# logic.net
KiCad netlist of a schematic drawn in EAGLE
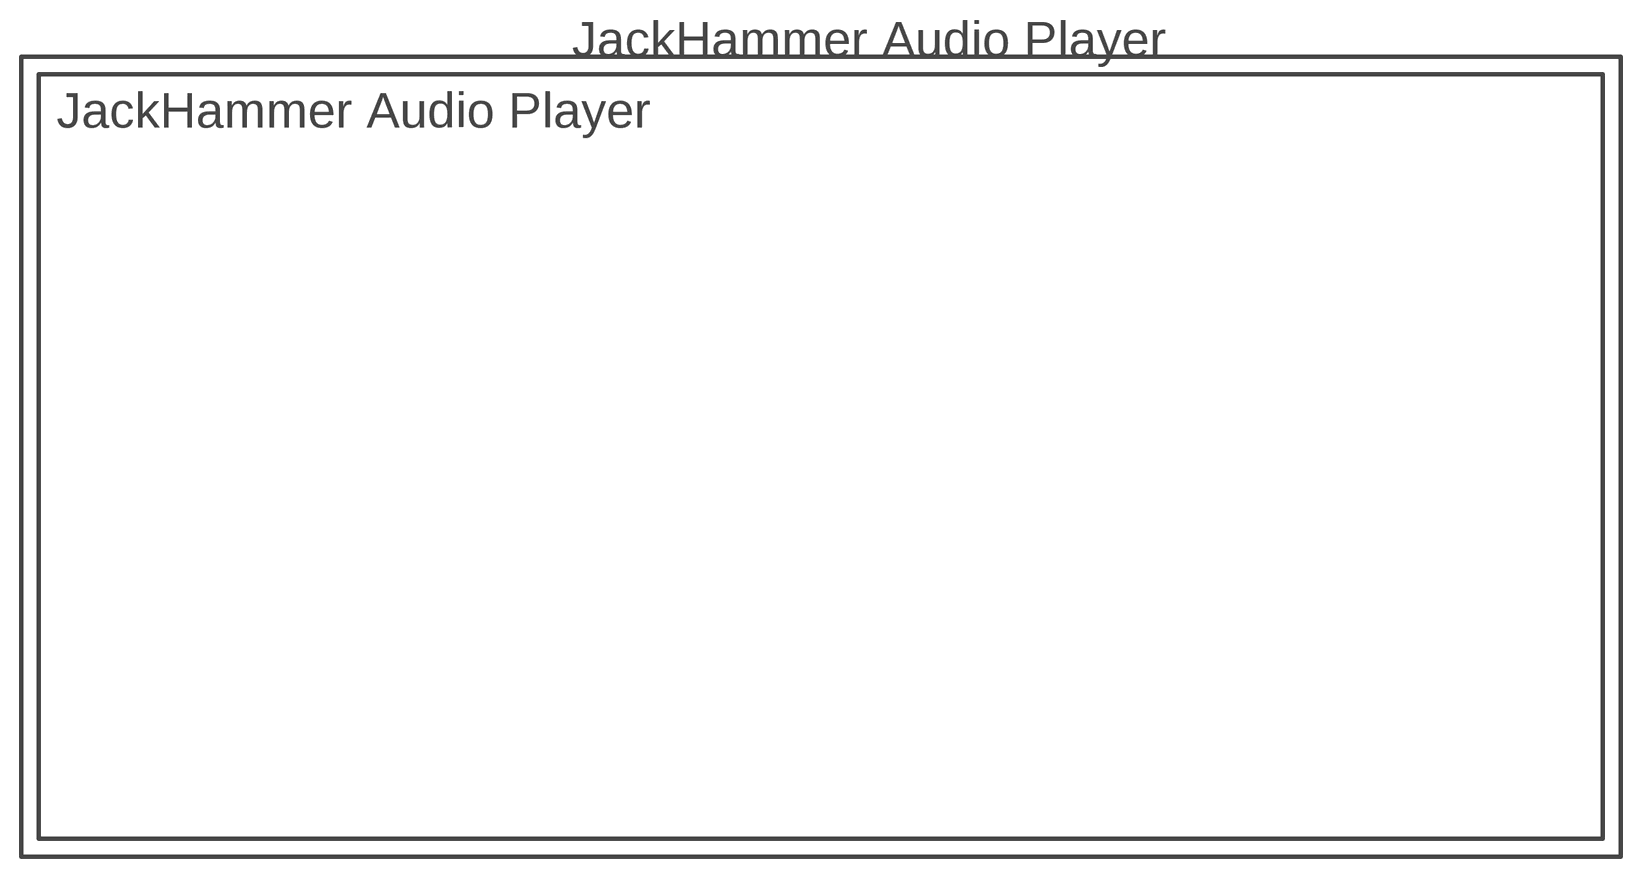
[diagram p0: schematic, sheet 1]
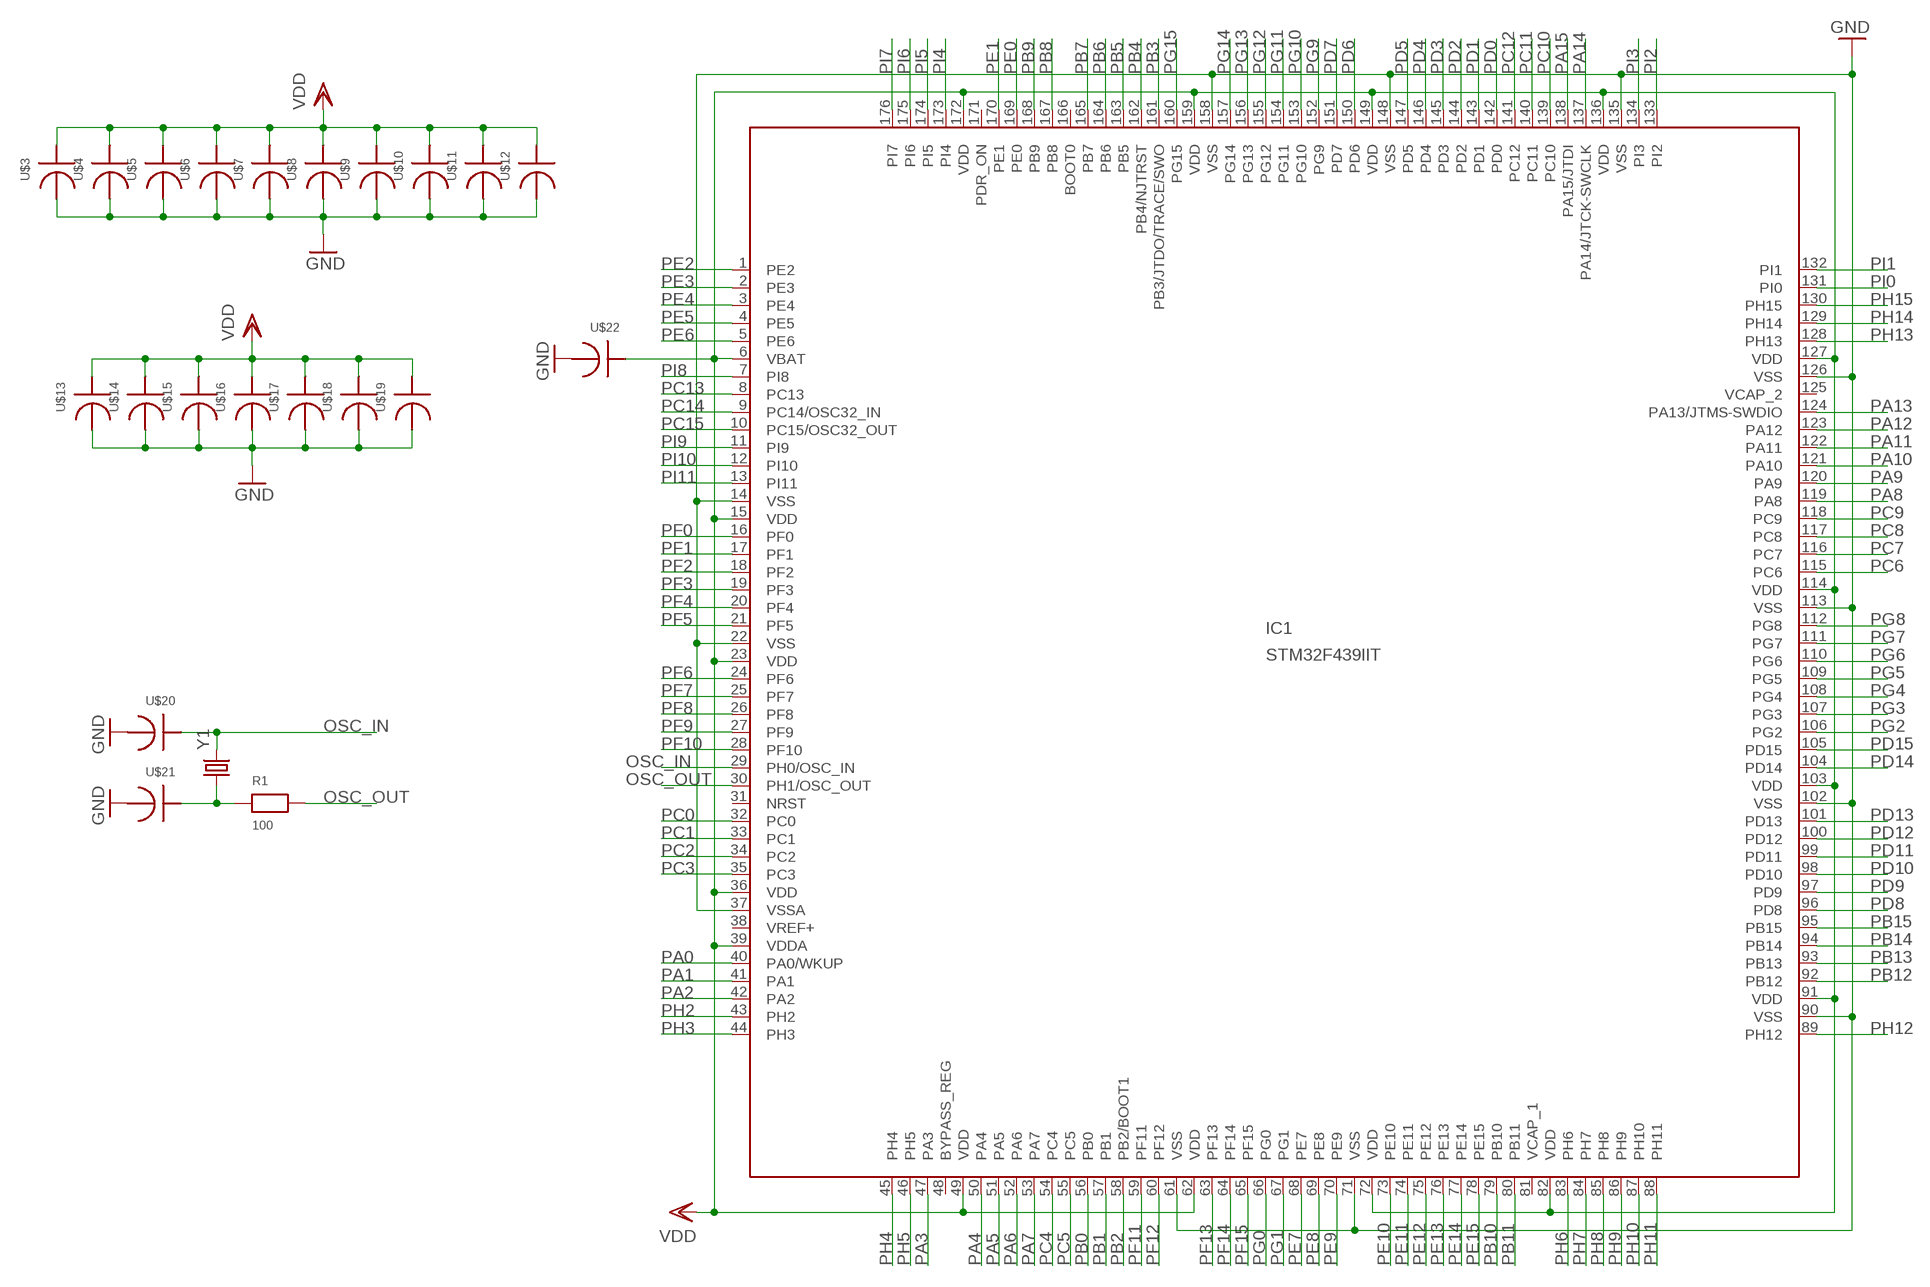
[diagram p1: schematic, sheet 2]
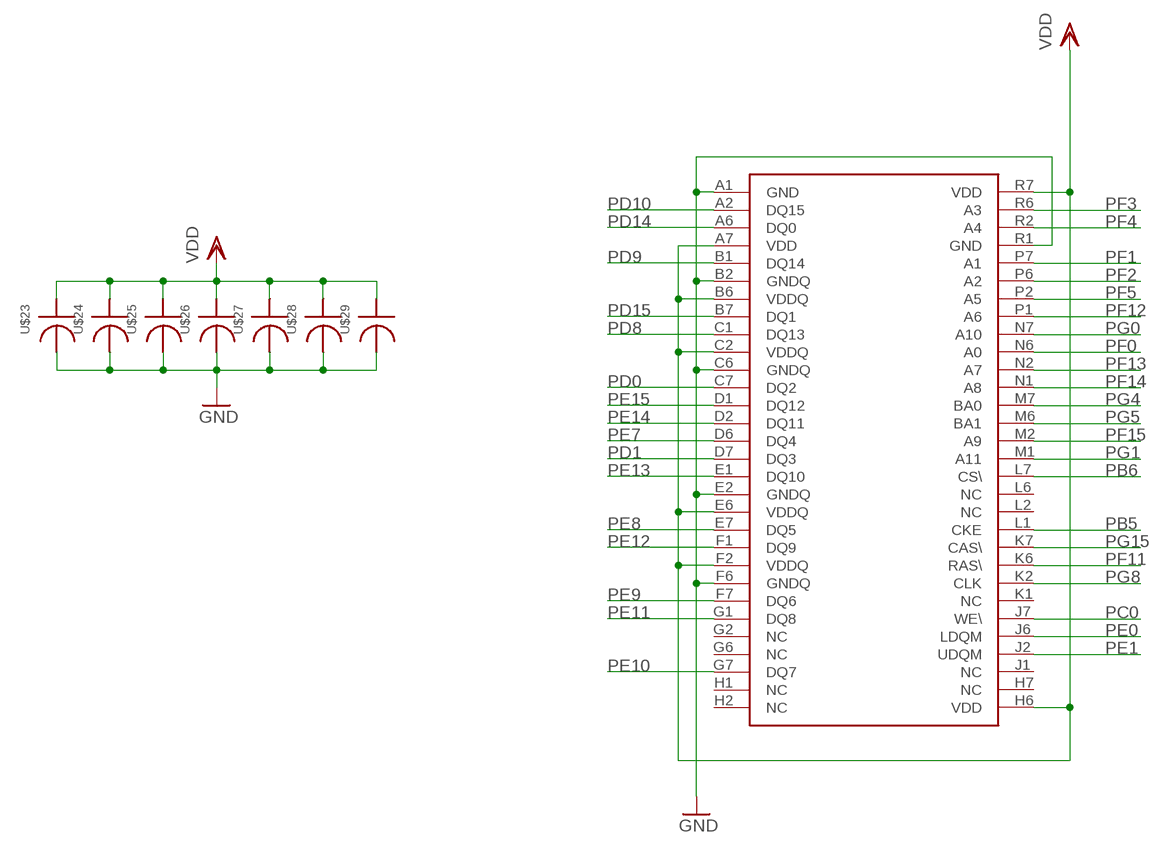
[diagram p2: schematic, sheet 3]
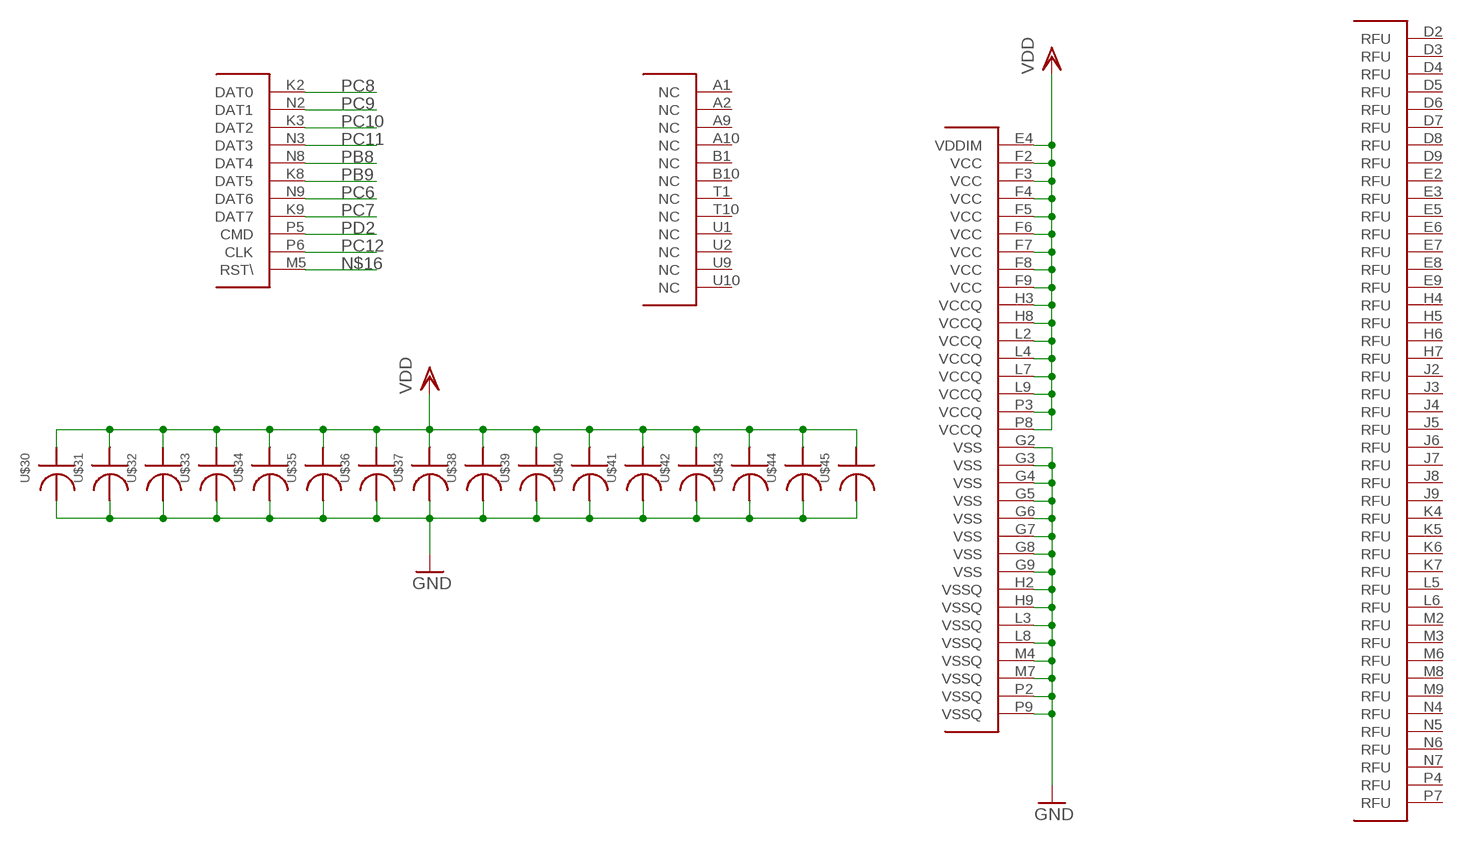
[diagram p3: schematic, sheet 4]
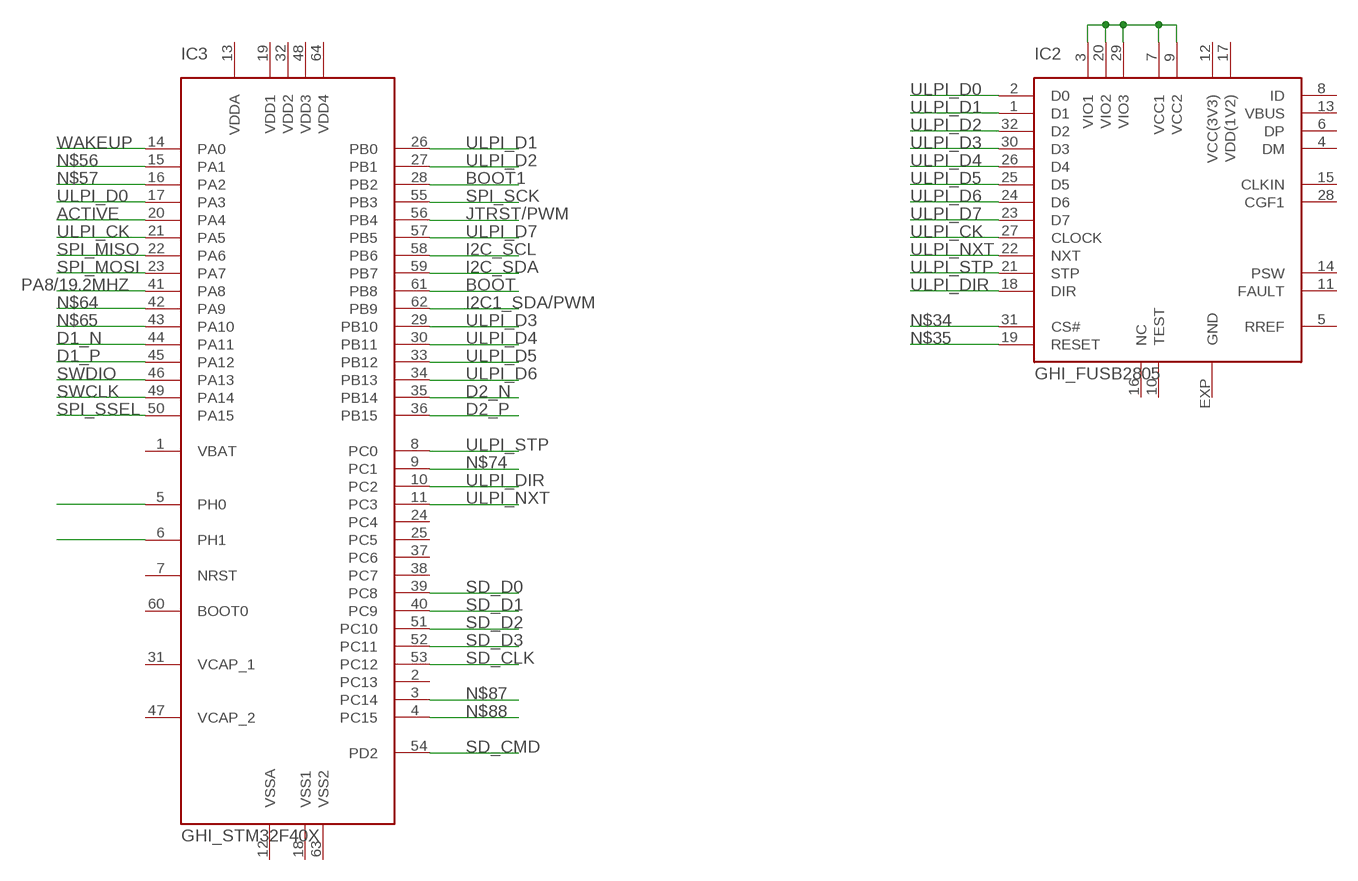
[diagram p4: schematic, sheet 5]
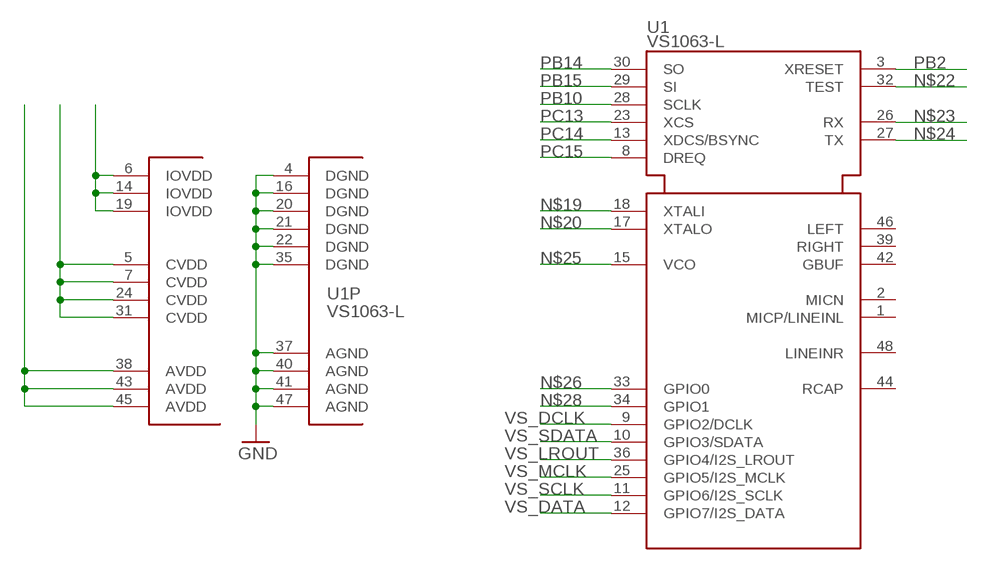
[diagram p5: schematic, sheet 6]

(export (version "E")
  (design (tool "Eeschema 10.0.6"))
  (components
    (comp (ref "U1")
      (value "VS1063-L")
      (footprint "eagle-import:LQFP48")
      (libsource (lib "eagle-import") (part "VS1063-L"))
    )
    (comp (ref "U$1")
      (value "MTFC4GACAANA-4M")
      (footprint "eagle-import:BGA-100")
      (libsource (lib "eagle-import") (part "MTFC4GACAANA-4M"))
    )
    (comp (ref "U$30")
      (value "PCAP0402LEVEL3")
      (footprint "eagle-import:R0402")
      (libsource (lib "eagle-import") (part "PCAP0402LEVEL3"))
    )
    (comp (ref "U$31")
      (value "PCAP0402LEVEL3")
      (footprint "eagle-import:R0402")
      (libsource (lib "eagle-import") (part "PCAP0402LEVEL3"))
    )
    (comp (ref "U$32")
      (value "PCAP0402LEVEL3")
      (footprint "eagle-import:R0402")
      (libsource (lib "eagle-import") (part "PCAP0402LEVEL3"))
    )
    (comp (ref "U$33")
      (value "PCAP0402LEVEL3")
      (footprint "eagle-import:R0402")
      (libsource (lib "eagle-import") (part "PCAP0402LEVEL3"))
    )
    (comp (ref "U$34")
      (value "PCAP0402LEVEL3")
      (footprint "eagle-import:R0402")
      (libsource (lib "eagle-import") (part "PCAP0402LEVEL3"))
    )
    (comp (ref "U$35")
      (value "PCAP0402LEVEL3")
      (footprint "eagle-import:R0402")
      (libsource (lib "eagle-import") (part "PCAP0402LEVEL3"))
    )
    (comp (ref "U$36")
      (value "PCAP0402LEVEL3")
      (footprint "eagle-import:R0402")
      (libsource (lib "eagle-import") (part "PCAP0402LEVEL3"))
    )
    (comp (ref "U$37")
      (value "PCAP0402LEVEL3")
      (footprint "eagle-import:R0402")
      (libsource (lib "eagle-import") (part "PCAP0402LEVEL3"))
    )
    (comp (ref "U$38")
      (value "PCAP0402LEVEL3")
      (footprint "eagle-import:R0402")
      (libsource (lib "eagle-import") (part "PCAP0402LEVEL3"))
    )
    (comp (ref "U$39")
      (value "PCAP0402LEVEL3")
      (footprint "eagle-import:R0402")
      (libsource (lib "eagle-import") (part "PCAP0402LEVEL3"))
    )
    (comp (ref "U$40")
      (value "PCAP0402LEVEL3")
      (footprint "eagle-import:R0402")
      (libsource (lib "eagle-import") (part "PCAP0402LEVEL3"))
    )
    (comp (ref "U$41")
      (value "PCAP0402LEVEL3")
      (footprint "eagle-import:R0402")
      (libsource (lib "eagle-import") (part "PCAP0402LEVEL3"))
    )
    (comp (ref "U$42")
      (value "PCAP0402LEVEL3")
      (footprint "eagle-import:R0402")
      (libsource (lib "eagle-import") (part "PCAP0402LEVEL3"))
    )
    (comp (ref "U$43")
      (value "PCAP0402LEVEL3")
      (footprint "eagle-import:R0402")
      (libsource (lib "eagle-import") (part "PCAP0402LEVEL3"))
    )
    (comp (ref "U$44")
      (value "PCAP0402LEVEL3")
      (footprint "eagle-import:R0402")
      (libsource (lib "eagle-import") (part "PCAP0402LEVEL3"))
    )
    (comp (ref "U$45")
      (value "PCAP0402LEVEL3")
      (footprint "eagle-import:R0402")
      (libsource (lib "eagle-import") (part "PCAP0402LEVEL3"))
    )
    (comp (ref "U$2")
      (value "IS42S16400J-BGA60")
      (footprint "eagle-import:BGA-60")
      (libsource (lib "eagle-import") (part "IS42S16400J-BGA60"))
    )
    (comp (ref "U$23")
      (value "PCAP0402LEVEL3")
      (footprint "eagle-import:R0402")
      (libsource (lib "eagle-import") (part "PCAP0402LEVEL3"))
    )
    (comp (ref "U$24")
      (value "PCAP0402LEVEL3")
      (footprint "eagle-import:R0402")
      (libsource (lib "eagle-import") (part "PCAP0402LEVEL3"))
    )
    (comp (ref "U$25")
      (value "PCAP0402LEVEL3")
      (footprint "eagle-import:R0402")
      (libsource (lib "eagle-import") (part "PCAP0402LEVEL3"))
    )
    (comp (ref "U$26")
      (value "PCAP0402LEVEL3")
      (footprint "eagle-import:R0402")
      (libsource (lib "eagle-import") (part "PCAP0402LEVEL3"))
    )
    (comp (ref "U$27")
      (value "PCAP0402LEVEL3")
      (footprint "eagle-import:R0402")
      (libsource (lib "eagle-import") (part "PCAP0402LEVEL3"))
    )
    (comp (ref "U$28")
      (value "PCAP0402LEVEL3")
      (footprint "eagle-import:R0402")
      (libsource (lib "eagle-import") (part "PCAP0402LEVEL3"))
    )
    (comp (ref "U$29")
      (value "PCAP0402LEVEL3")
      (footprint "eagle-import:R0402")
      (libsource (lib "eagle-import") (part "PCAP0402LEVEL3"))
    )
    (comp (ref "IC2")
      (value "GHI_FUSB2805")
      (footprint "eagle-import:GHI_MLP32")
      (libsource (lib "eagle-import") (part "GHI_FUSB2805"))
    )
    (comp (ref "IC3")
      (value "GHI_STM32F40X")
      (footprint "eagle-import:GHI_LQFP64")
      (libsource (lib "eagle-import") (part "GHI_STM32F40X"))
    )
    (comp (ref "IC1")
      (value "STM32F439IIT")
      (footprint "eagle-import:LQFP-176")
      (libsource (lib "eagle-import") (part "STM32F439IIT"))
    )
    (comp (ref "R1")
      (value "100")
      (footprint "eagle-import:R0402")
      (libsource (lib "eagle-import") (part "PRES0402LEVEL3"))
    )
    (comp (ref "U$3")
      (value "PCAP0402LEVEL3")
      (footprint "eagle-import:R0402")
      (libsource (lib "eagle-import") (part "PCAP0402LEVEL3"))
    )
    (comp (ref "U$4")
      (value "PCAP0402LEVEL3")
      (footprint "eagle-import:R0402")
      (libsource (lib "eagle-import") (part "PCAP0402LEVEL3"))
    )
    (comp (ref "U$5")
      (value "PCAP0402LEVEL3")
      (footprint "eagle-import:R0402")
      (libsource (lib "eagle-import") (part "PCAP0402LEVEL3"))
    )
    (comp (ref "U$6")
      (value "PCAP0402LEVEL3")
      (footprint "eagle-import:R0402")
      (libsource (lib "eagle-import") (part "PCAP0402LEVEL3"))
    )
    (comp (ref "U$7")
      (value "PCAP0402LEVEL3")
      (footprint "eagle-import:R0402")
      (libsource (lib "eagle-import") (part "PCAP0402LEVEL3"))
    )
    (comp (ref "U$8")
      (value "PCAP0402LEVEL3")
      (footprint "eagle-import:R0402")
      (libsource (lib "eagle-import") (part "PCAP0402LEVEL3"))
    )
    (comp (ref "U$9")
      (value "PCAP0402LEVEL3")
      (footprint "eagle-import:R0402")
      (libsource (lib "eagle-import") (part "PCAP0402LEVEL3"))
    )
    (comp (ref "U$10")
      (value "PCAP0402LEVEL3")
      (footprint "eagle-import:R0402")
      (libsource (lib "eagle-import") (part "PCAP0402LEVEL3"))
    )
    (comp (ref "U$11")
      (value "PCAP0402LEVEL3")
      (footprint "eagle-import:R0402")
      (libsource (lib "eagle-import") (part "PCAP0402LEVEL3"))
    )
    (comp (ref "U$12")
      (value "PCAP0402LEVEL3")
      (footprint "eagle-import:R0402")
      (libsource (lib "eagle-import") (part "PCAP0402LEVEL3"))
    )
    (comp (ref "U$13")
      (value "PCAP0402LEVEL3")
      (footprint "eagle-import:R0402")
      (libsource (lib "eagle-import") (part "PCAP0402LEVEL3"))
    )
    (comp (ref "U$14")
      (value "PCAP0402LEVEL3")
      (footprint "eagle-import:R0402")
      (libsource (lib "eagle-import") (part "PCAP0402LEVEL3"))
    )
    (comp (ref "U$15")
      (value "PCAP0402LEVEL3")
      (footprint "eagle-import:R0402")
      (libsource (lib "eagle-import") (part "PCAP0402LEVEL3"))
    )
    (comp (ref "U$16")
      (value "PCAP0402LEVEL3")
      (footprint "eagle-import:R0402")
      (libsource (lib "eagle-import") (part "PCAP0402LEVEL3"))
    )
    (comp (ref "U$17")
      (value "PCAP0402LEVEL3")
      (footprint "eagle-import:R0402")
      (libsource (lib "eagle-import") (part "PCAP0402LEVEL3"))
    )
    (comp (ref "U$18")
      (value "PCAP0402LEVEL3")
      (footprint "eagle-import:R0402")
      (libsource (lib "eagle-import") (part "PCAP0402LEVEL3"))
    )
    (comp (ref "U$19")
      (value "PCAP0402LEVEL3")
      (footprint "eagle-import:R0402")
      (libsource (lib "eagle-import") (part "PCAP0402LEVEL3"))
    )
    (comp (ref "U$20")
      (value "PCAP0402LEVEL3")
      (footprint "eagle-import:R0402")
      (libsource (lib "eagle-import") (part "PCAP0402LEVEL3"))
    )
    (comp (ref "U$21")
      (value "PCAP0402LEVEL3")
      (footprint "eagle-import:R0402")
      (libsource (lib "eagle-import") (part "PCAP0402LEVEL3"))
    )
    (comp (ref "U$22")
      (value "PCAP0402LEVEL3")
      (footprint "eagle-import:R0402")
      (libsource (lib "eagle-import") (part "PCAP0402LEVEL3"))
    )
    (comp (ref "Y1")
      (value "CRYSTALHC49US")
      (footprint "eagle-import:HC49US")
      (libsource (lib "eagle-import") (part "CRYSTALHC49US"))
    )
  )
  (nets
    (net (code "1") (name "ACTIVE") (class "Default")
      (node (ref "IC3") (pin "20") (pinfunction "PA4_20") (pintype "bidirectional"))
    )
    (net (code "2") (name "BOOT") (class "Default")
      (node (ref "IC3") (pin "61") (pinfunction "PB8_61") (pintype "bidirectional"))
    )
    (net (code "3") (name "BOOT1") (class "Default")
      (node (ref "IC3") (pin "28") (pinfunction "PB2_28") (pintype "bidirectional"))
    )
    (net (code "4") (name "D1_N") (class "Default")
      (node (ref "IC3") (pin "44") (pinfunction "PA11_44") (pintype "bidirectional"))
    )
    (net (code "5") (name "D1_P") (class "Default")
      (node (ref "IC3") (pin "45") (pinfunction "PA12_45") (pintype "bidirectional"))
    )
    (net (code "6") (name "D2_N") (class "Default")
      (node (ref "IC3") (pin "35") (pinfunction "PB14_35") (pintype "bidirectional"))
    )
    (net (code "7") (name "D2_P") (class "Default")
      (node (ref "IC3") (pin "36") (pinfunction "PB15_36") (pintype "bidirectional"))
    )
    (net (code "8") (name "GND") (class "Default")
      (node (ref "IC1") (pin "102") (pinfunction "VSS_102") (pintype "power_in"))
      (node (ref "IC1") (pin "113") (pinfunction "VSS_113") (pintype "power_in"))
      (node (ref "IC1") (pin "126") (pinfunction "VSS_126") (pintype "power_in"))
      (node (ref "IC1") (pin "135") (pinfunction "VSS_135") (pintype "power_in"))
      (node (ref "IC1") (pin "14") (pinfunction "VSS_14") (pintype "power_in"))
      (node (ref "IC1") (pin "148") (pinfunction "VSS_148") (pintype "power_in"))
      (node (ref "IC1") (pin "158") (pinfunction "VSS_158") (pintype "power_in"))
      (node (ref "IC1") (pin "22") (pinfunction "VSS_22") (pintype "power_in"))
      (node (ref "IC1") (pin "37") (pinfunction "VSSA_37") (pintype "power_in"))
      (node (ref "IC1") (pin "61") (pinfunction "VSS_61") (pintype "power_in"))
      (node (ref "IC1") (pin "71") (pinfunction "VSS_71") (pintype "power_in"))
      (node (ref "IC1") (pin "90") (pinfunction "VSS_90") (pintype "power_in"))
      (node (ref "U$1") (pin "G2") (pinfunction "VSS_G2") (pintype "bidirectional"))
      (node (ref "U$1") (pin "G3") (pinfunction "VSS_G3") (pintype "bidirectional"))
      (node (ref "U$1") (pin "G4") (pinfunction "VSS_G4") (pintype "bidirectional"))
      (node (ref "U$1") (pin "G5") (pinfunction "VSS_G5") (pintype "bidirectional"))
      (node (ref "U$1") (pin "G6") (pinfunction "VSS_G6") (pintype "bidirectional"))
      (node (ref "U$1") (pin "G7") (pinfunction "VSS_G7") (pintype "bidirectional"))
      (node (ref "U$1") (pin "G8") (pinfunction "VSS_G8") (pintype "bidirectional"))
      (node (ref "U$1") (pin "G9") (pinfunction "VSS_G9") (pintype "bidirectional"))
      (node (ref "U$1") (pin "H2") (pinfunction "VSSQ_H2") (pintype "bidirectional"))
      (node (ref "U$1") (pin "H9") (pinfunction "VSSQ_H9") (pintype "bidirectional"))
      (node (ref "U$1") (pin "L3") (pinfunction "VSSQ_L3") (pintype "bidirectional"))
      (node (ref "U$1") (pin "L8") (pinfunction "VSSQ_L8") (pintype "bidirectional"))
      (node (ref "U$1") (pin "M4") (pinfunction "VSSQ_M4") (pintype "bidirectional"))
      (node (ref "U$1") (pin "M7") (pinfunction "VSSQ_M7") (pintype "bidirectional"))
      (node (ref "U$1") (pin "P2") (pinfunction "VSSQ_P2") (pintype "bidirectional"))
      (node (ref "U$1") (pin "P9") (pinfunction "VSSQ_P9") (pintype "bidirectional"))
      (node (ref "U$10") (pin "P$1") (pinfunction "P$1_P$1") (pintype "bidirectional"))
      (node (ref "U$11") (pin "P$1") (pinfunction "P$1_P$1") (pintype "bidirectional"))
      (node (ref "U$12") (pin "P$1") (pinfunction "P$1_P$1") (pintype "bidirectional"))
      (node (ref "U$13") (pin "P$1") (pinfunction "P$1_P$1") (pintype "bidirectional"))
      (node (ref "U$14") (pin "P$1") (pinfunction "P$1_P$1") (pintype "bidirectional"))
      (node (ref "U$15") (pin "P$1") (pinfunction "P$1_P$1") (pintype "bidirectional"))
      (node (ref "U$16") (pin "P$1") (pinfunction "P$1_P$1") (pintype "bidirectional"))
      (node (ref "U$17") (pin "P$1") (pinfunction "P$1_P$1") (pintype "bidirectional"))
      (node (ref "U$18") (pin "P$1") (pinfunction "P$1_P$1") (pintype "bidirectional"))
      (node (ref "U$19") (pin "P$1") (pinfunction "P$1_P$1") (pintype "bidirectional"))
      (node (ref "U$2") (pin "A1") (pinfunction "GND_A1") (pintype "bidirectional"))
      (node (ref "U$2") (pin "B2") (pinfunction "GNDQ_B2") (pintype "bidirectional"))
      (node (ref "U$2") (pin "C6") (pinfunction "GNDQ_C6") (pintype "bidirectional"))
      (node (ref "U$2") (pin "E2") (pinfunction "GNDQ_E2") (pintype "bidirectional"))
      (node (ref "U$2") (pin "F6") (pinfunction "GNDQ_F6") (pintype "bidirectional"))
      (node (ref "U$2") (pin "R1") (pinfunction "GND_R1") (pintype "bidirectional"))
      (node (ref "U$20") (pin "P$1") (pinfunction "P$1_P$1") (pintype "bidirectional"))
      (node (ref "U$21") (pin "P$1") (pinfunction "P$1_P$1") (pintype "bidirectional"))
      (node (ref "U$22") (pin "P$1") (pinfunction "P$1_P$1") (pintype "bidirectional"))
      (node (ref "U$23") (pin "P$1") (pinfunction "P$1_P$1") (pintype "bidirectional"))
      (node (ref "U$24") (pin "P$1") (pinfunction "P$1_P$1") (pintype "bidirectional"))
      (node (ref "U$25") (pin "P$1") (pinfunction "P$1_P$1") (pintype "bidirectional"))
      (node (ref "U$26") (pin "P$1") (pinfunction "P$1_P$1") (pintype "bidirectional"))
      (node (ref "U$27") (pin "P$1") (pinfunction "P$1_P$1") (pintype "bidirectional"))
      (node (ref "U$28") (pin "P$1") (pinfunction "P$1_P$1") (pintype "bidirectional"))
      (node (ref "U$29") (pin "P$1") (pinfunction "P$1_P$1") (pintype "bidirectional"))
      (node (ref "U$3") (pin "P$1") (pinfunction "P$1_P$1") (pintype "bidirectional"))
      (node (ref "U$30") (pin "P$1") (pinfunction "P$1_P$1") (pintype "bidirectional"))
      (node (ref "U$31") (pin "P$1") (pinfunction "P$1_P$1") (pintype "bidirectional"))
      (node (ref "U$32") (pin "P$1") (pinfunction "P$1_P$1") (pintype "bidirectional"))
      (node (ref "U$33") (pin "P$1") (pinfunction "P$1_P$1") (pintype "bidirectional"))
      (node (ref "U$34") (pin "P$1") (pinfunction "P$1_P$1") (pintype "bidirectional"))
      (node (ref "U$35") (pin "P$1") (pinfunction "P$1_P$1") (pintype "bidirectional"))
      (node (ref "U$36") (pin "P$1") (pinfunction "P$1_P$1") (pintype "bidirectional"))
      (node (ref "U$37") (pin "P$1") (pinfunction "P$1_P$1") (pintype "bidirectional"))
      (node (ref "U$38") (pin "P$1") (pinfunction "P$1_P$1") (pintype "bidirectional"))
      (node (ref "U$39") (pin "P$1") (pinfunction "P$1_P$1") (pintype "bidirectional"))
      (node (ref "U$4") (pin "P$1") (pinfunction "P$1_P$1") (pintype "bidirectional"))
      (node (ref "U$40") (pin "P$1") (pinfunction "P$1_P$1") (pintype "bidirectional"))
      (node (ref "U$41") (pin "P$1") (pinfunction "P$1_P$1") (pintype "bidirectional"))
      (node (ref "U$42") (pin "P$1") (pinfunction "P$1_P$1") (pintype "bidirectional"))
      (node (ref "U$43") (pin "P$1") (pinfunction "P$1_P$1") (pintype "bidirectional"))
      (node (ref "U$44") (pin "P$1") (pinfunction "P$1_P$1") (pintype "bidirectional"))
      (node (ref "U$45") (pin "P$1") (pinfunction "P$1_P$1") (pintype "bidirectional"))
      (node (ref "U$5") (pin "P$1") (pinfunction "P$1_P$1") (pintype "bidirectional"))
      (node (ref "U$6") (pin "P$1") (pinfunction "P$1_P$1") (pintype "bidirectional"))
      (node (ref "U$7") (pin "P$1") (pinfunction "P$1_P$1") (pintype "bidirectional"))
      (node (ref "U$8") (pin "P$1") (pinfunction "P$1_P$1") (pintype "bidirectional"))
      (node (ref "U$9") (pin "P$1") (pinfunction "P$1_P$1") (pintype "bidirectional"))
      (node (ref "U1") (pin "16") (pinfunction "DGND_16") (pintype "power_in"))
      (node (ref "U1") (pin "20") (pinfunction "DGND_20") (pintype "power_in"))
      (node (ref "U1") (pin "21") (pinfunction "DGND_21") (pintype "power_in"))
      (node (ref "U1") (pin "22") (pinfunction "DGND_22") (pintype "power_in"))
      (node (ref "U1") (pin "35") (pinfunction "DGND_35") (pintype "power_in"))
      (node (ref "U1") (pin "37") (pinfunction "AGND_37") (pintype "power_in"))
      (node (ref "U1") (pin "4") (pinfunction "DGND_4") (pintype "power_in"))
      (node (ref "U1") (pin "40") (pinfunction "AGND_40") (pintype "power_in"))
      (node (ref "U1") (pin "41") (pinfunction "AGND_41") (pintype "power_in"))
      (node (ref "U1") (pin "47") (pinfunction "AGND_47") (pintype "power_in"))
    )
    (net (code "9") (name "I2C1_SDA{slash}PWM") (class "Default")
      (node (ref "IC3") (pin "62") (pinfunction "PB9_62") (pintype "bidirectional"))
    )
    (net (code "10") (name "I2C_SCL") (class "Default")
      (node (ref "IC3") (pin "58") (pinfunction "PB6_58") (pintype "bidirectional"))
    )
    (net (code "11") (name "I2C_SDA") (class "Default")
      (node (ref "IC3") (pin "59") (pinfunction "PB7_59") (pintype "bidirectional"))
    )
    (net (code "12") (name "JTRST{slash}PWM") (class "Default")
      (node (ref "IC3") (pin "56") (pinfunction "PB4_56") (pintype "bidirectional"))
    )
    (net (code "13") (name "N$16") (class "Default")
      (node (ref "U$1") (pin "M5") (pinfunction "RST\\_M5") (pintype "bidirectional"))
    )
    (net (code "14") (name "N$19") (class "Default")
      (node (ref "U1") (pin "18") (pinfunction "XTALI_18") (pintype "input"))
    )
    (net (code "15") (name "N$20") (class "Default")
      (node (ref "U1") (pin "17") (pinfunction "XTALO_17") (pintype "output"))
    )
    (net (code "16") (name "N$22") (class "Default")
      (node (ref "U1") (pin "32") (pinfunction "TEST_32") (pintype "input"))
    )
    (net (code "17") (name "N$23") (class "Default")
      (node (ref "U1") (pin "26") (pinfunction "RX_26") (pintype "input"))
    )
    (net (code "18") (name "N$24") (class "Default")
      (node (ref "U1") (pin "27") (pinfunction "TX_27") (pintype "output"))
    )
    (net (code "19") (name "N$25") (class "Default")
      (node (ref "U1") (pin "15") (pinfunction "VCO_15") (pintype "output"))
    )
    (net (code "20") (name "N$26") (class "Default")
      (node (ref "U1") (pin "33") (pinfunction "GPIO0_33") (pintype "bidirectional"))
    )
    (net (code "21") (name "N$28") (class "Default")
      (node (ref "U1") (pin "34") (pinfunction "GPIO1_34") (pintype "bidirectional"))
    )
    (net (code "22") (name "N$34") (class "Default")
      (node (ref "IC2") (pin "31") (pinfunction "CS#_31") (pintype "bidirectional"))
    )
    (net (code "23") (name "N$35") (class "Default")
      (node (ref "IC2") (pin "19") (pinfunction "RESET_19") (pintype "bidirectional"))
    )
    (net (code "24") (name "N$56") (class "Default")
      (node (ref "IC3") (pin "15") (pinfunction "PA1_15") (pintype "bidirectional"))
    )
    (net (code "25") (name "N$57") (class "Default")
      (node (ref "IC3") (pin "16") (pinfunction "PA2_16") (pintype "bidirectional"))
    )
    (net (code "26") (name "N$64") (class "Default")
      (node (ref "IC3") (pin "42") (pinfunction "PA9_42") (pintype "bidirectional"))
    )
    (net (code "27") (name "N$65") (class "Default")
      (node (ref "IC3") (pin "43") (pinfunction "PA10_43") (pintype "bidirectional"))
    )
    (net (code "28") (name "N$74") (class "Default")
      (node (ref "IC3") (pin "9") (pinfunction "PC1_9") (pintype "bidirectional"))
    )
    (net (code "29") (name "N$87") (class "Default")
      (node (ref "IC3") (pin "3") (pinfunction "PC14_3") (pintype "bidirectional"))
    )
    (net (code "30") (name "N$88") (class "Default")
      (node (ref "IC3") (pin "4") (pinfunction "PC15_4") (pintype "bidirectional"))
    )
    (net (code "31") (name "Net-(IC2-VCC1)") (class "Default")
      (node (ref "IC2") (pin "20") (pinfunction "VIO2_20") (pintype "bidirectional"))
      (node (ref "IC2") (pin "29") (pinfunction "VIO3_29") (pintype "bidirectional"))
      (node (ref "IC2") (pin "3") (pinfunction "VIO1_3") (pintype "bidirectional"))
      (node (ref "IC2") (pin "7") (pinfunction "VCC1_7") (pintype "bidirectional"))
      (node (ref "IC2") (pin "9") (pinfunction "VCC2_9") (pintype "bidirectional"))
    )
    (net (code "32") (name "Net-(R1-PadP$1)") (class "Default")
      (node (ref "R1") (pin "P$1") (pinfunction "P$1_P$1") (pintype "bidirectional"))
      (node (ref "U$21") (pin "P$2") (pinfunction "P$2_P$2") (pintype "bidirectional"))
      (node (ref "Y1") (pin "1") (pinfunction "1_1") (pintype "passive"))
    )
    (net (code "33") (name "Net-(U1B-AVDD-Pad38)") (class "Default")
      (node (ref "U1") (pin "38") (pinfunction "AVDD_38") (pintype "power_in"))
      (node (ref "U1") (pin "43") (pinfunction "AVDD_43") (pintype "power_in"))
      (node (ref "U1") (pin "45") (pinfunction "AVDD_45") (pintype "power_in"))
    )
    (net (code "34") (name "Net-(U1B-CVDD-Pad24)") (class "Default")
      (node (ref "U1") (pin "24") (pinfunction "CVDD_24") (pintype "power_in"))
      (node (ref "U1") (pin "31") (pinfunction "CVDD_31") (pintype "power_in"))
      (node (ref "U1") (pin "5") (pinfunction "CVDD_5") (pintype "power_in"))
      (node (ref "U1") (pin "7") (pinfunction "CVDD_7") (pintype "power_in"))
    )
    (net (code "35") (name "Net-(U1B-IOVDD-Pad14)") (class "Default")
      (node (ref "U1") (pin "14") (pinfunction "IOVDD_14") (pintype "power_in"))
      (node (ref "U1") (pin "19") (pinfunction "IOVDD_19") (pintype "power_in"))
      (node (ref "U1") (pin "6") (pinfunction "IOVDD_6") (pintype "power_in"))
    )
    (net (code "36") (name "OSC_IN") (class "Default")
      (node (ref "IC1") (pin "29") (pinfunction "PH0/OSC_IN_29") (pintype "bidirectional"))
      (node (ref "U$20") (pin "P$2") (pinfunction "P$2_P$2") (pintype "bidirectional"))
      (node (ref "Y1") (pin "2") (pinfunction "2_2") (pintype "passive"))
    )
    (net (code "37") (name "OSC_OUT") (class "Default")
      (node (ref "IC1") (pin "30") (pinfunction "PH1/OSC_OUT_30") (pintype "bidirectional"))
      (node (ref "R1") (pin "P$2") (pinfunction "P$2_P$2") (pintype "bidirectional"))
    )
    (net (code "38") (name "PA0") (class "Default")
      (node (ref "IC1") (pin "40") (pinfunction "PA0/WKUP_40") (pintype "bidirectional"))
    )
    (net (code "39") (name "PA1") (class "Default")
      (node (ref "IC1") (pin "41") (pinfunction "PA1_41") (pintype "bidirectional"))
    )
    (net (code "40") (name "PA2") (class "Default")
      (node (ref "IC1") (pin "42") (pinfunction "PA2_42") (pintype "bidirectional"))
    )
    (net (code "41") (name "PA3") (class "Default")
      (node (ref "IC1") (pin "47") (pinfunction "PA3_47") (pintype "bidirectional"))
    )
    (net (code "42") (name "PA4") (class "Default")
      (node (ref "IC1") (pin "50") (pinfunction "PA4_50") (pintype "bidirectional"))
    )
    (net (code "43") (name "PA5") (class "Default")
      (node (ref "IC1") (pin "51") (pinfunction "PA5_51") (pintype "bidirectional"))
    )
    (net (code "44") (name "PA6") (class "Default")
      (node (ref "IC1") (pin "52") (pinfunction "PA6_52") (pintype "bidirectional"))
    )
    (net (code "45") (name "PA7") (class "Default")
      (node (ref "IC1") (pin "53") (pinfunction "PA7_53") (pintype "bidirectional"))
    )
    (net (code "46") (name "PA8") (class "Default")
      (node (ref "IC1") (pin "119") (pinfunction "PA8_119") (pintype "bidirectional"))
    )
    (net (code "47") (name "PA8{slash}19.2MHZ") (class "Default")
      (node (ref "IC3") (pin "41") (pinfunction "PA8_41") (pintype "bidirectional"))
    )
    (net (code "48") (name "PA9") (class "Default")
      (node (ref "IC1") (pin "120") (pinfunction "PA9_120") (pintype "bidirectional"))
    )
    (net (code "49") (name "PA10") (class "Default")
      (node (ref "IC1") (pin "121") (pinfunction "PA10_121") (pintype "bidirectional"))
    )
    (net (code "50") (name "PA11") (class "Default")
      (node (ref "IC1") (pin "122") (pinfunction "PA11_122") (pintype "bidirectional"))
    )
    (net (code "51") (name "PA12") (class "Default")
      (node (ref "IC1") (pin "123") (pinfunction "PA12_123") (pintype "bidirectional"))
    )
    (net (code "52") (name "PA13") (class "Default")
      (node (ref "IC1") (pin "124") (pinfunction "PA13/JTMS-SWDIO_124") (pintype "bidirectional"))
    )
    (net (code "53") (name "PA14") (class "Default")
      (node (ref "IC1") (pin "137") (pinfunction "PA14/JTCK-SWCLK_137") (pintype "bidirectional"))
    )
    (net (code "54") (name "PA15") (class "Default")
      (node (ref "IC1") (pin "138") (pinfunction "PA15/JTDI_138") (pintype "bidirectional"))
    )
    (net (code "55") (name "PB0") (class "Default")
      (node (ref "IC1") (pin "56") (pinfunction "PB0_56") (pintype "bidirectional"))
    )
    (net (code "56") (name "PB1") (class "Default")
      (node (ref "IC1") (pin "57") (pinfunction "PB1_57") (pintype "bidirectional"))
    )
    (net (code "57") (name "PB2") (class "Default")
      (node (ref "IC1") (pin "58") (pinfunction "PB2/BOOT1_58") (pintype "bidirectional"))
      (node (ref "U1") (pin "3") (pinfunction "XRESET_3") (pintype "input"))
    )
    (net (code "58") (name "PB3") (class "Default")
      (node (ref "IC1") (pin "161") (pinfunction "PB3/JTDO/TRACE/SWO_161") (pintype "bidirectional"))
    )
    (net (code "59") (name "PB4") (class "Default")
      (node (ref "IC1") (pin "162") (pinfunction "PB4/NJTRST_162") (pintype "bidirectional"))
    )
    (net (code "60") (name "PB5") (class "Default")
      (node (ref "IC1") (pin "163") (pinfunction "PB5_163") (pintype "bidirectional"))
      (node (ref "U$2") (pin "L1") (pinfunction "CKE_L1") (pintype "bidirectional"))
    )
    (net (code "61") (name "PB6") (class "Default")
      (node (ref "IC1") (pin "164") (pinfunction "PB6_164") (pintype "bidirectional"))
      (node (ref "U$2") (pin "L7") (pinfunction "CS\\_L7") (pintype "bidirectional"))
    )
    (net (code "62") (name "PB7") (class "Default")
      (node (ref "IC1") (pin "165") (pinfunction "PB7_165") (pintype "bidirectional"))
    )
    (net (code "63") (name "PB8") (class "Default")
      (node (ref "IC1") (pin "167") (pinfunction "PB8_167") (pintype "bidirectional"))
      (node (ref "U$1") (pin "N8") (pinfunction "DAT4_N8") (pintype "bidirectional"))
    )
    (net (code "64") (name "PB9") (class "Default")
      (node (ref "IC1") (pin "168") (pinfunction "PB9_168") (pintype "bidirectional"))
      (node (ref "U$1") (pin "K8") (pinfunction "DAT5_K8") (pintype "bidirectional"))
    )
    (net (code "65") (name "PB10") (class "Default")
      (node (ref "IC1") (pin "79") (pinfunction "PB10_79") (pintype "bidirectional"))
      (node (ref "U1") (pin "28") (pinfunction "SCLK_28") (pintype "input"))
    )
    (net (code "66") (name "PB11") (class "Default")
      (node (ref "IC1") (pin "80") (pinfunction "PB11_80") (pintype "bidirectional"))
    )
    (net (code "67") (name "PB12") (class "Default")
      (node (ref "IC1") (pin "92") (pinfunction "PB12_92") (pintype "bidirectional"))
    )
    (net (code "68") (name "PB13") (class "Default")
      (node (ref "IC1") (pin "93") (pinfunction "PB13_93") (pintype "bidirectional"))
    )
    (net (code "69") (name "PB14") (class "Default")
      (node (ref "IC1") (pin "94") (pinfunction "PB14_94") (pintype "bidirectional"))
      (node (ref "U1") (pin "30") (pinfunction "SO_30") (pintype "output"))
    )
    (net (code "70") (name "PB15") (class "Default")
      (node (ref "IC1") (pin "95") (pinfunction "PB15_95") (pintype "bidirectional"))
      (node (ref "U1") (pin "29") (pinfunction "SI_29") (pintype "input"))
    )
    (net (code "71") (name "PC0") (class "Default")
      (node (ref "IC1") (pin "32") (pinfunction "PC0_32") (pintype "bidirectional"))
      (node (ref "U$2") (pin "J7") (pinfunction "WE\\_J7") (pintype "bidirectional"))
    )
    (net (code "72") (name "PC1") (class "Default")
      (node (ref "IC1") (pin "33") (pinfunction "PC1_33") (pintype "bidirectional"))
    )
    (net (code "73") (name "PC2") (class "Default")
      (node (ref "IC1") (pin "34") (pinfunction "PC2_34") (pintype "bidirectional"))
    )
    (net (code "74") (name "PC3") (class "Default")
      (node (ref "IC1") (pin "35") (pinfunction "PC3_35") (pintype "bidirectional"))
    )
    (net (code "75") (name "PC4") (class "Default")
      (node (ref "IC1") (pin "54") (pinfunction "PC4_54") (pintype "bidirectional"))
    )
    (net (code "76") (name "PC5") (class "Default")
      (node (ref "IC1") (pin "55") (pinfunction "PC5_55") (pintype "bidirectional"))
    )
    (net (code "77") (name "PC6") (class "Default")
      (node (ref "IC1") (pin "115") (pinfunction "PC6_115") (pintype "bidirectional"))
      (node (ref "U$1") (pin "N9") (pinfunction "DAT6_N9") (pintype "bidirectional"))
    )
    (net (code "78") (name "PC7") (class "Default")
      (node (ref "IC1") (pin "116") (pinfunction "PC7_116") (pintype "bidirectional"))
      (node (ref "U$1") (pin "K9") (pinfunction "DAT7_K9") (pintype "bidirectional"))
    )
    (net (code "79") (name "PC8") (class "Default")
      (node (ref "IC1") (pin "117") (pinfunction "PC8_117") (pintype "bidirectional"))
      (node (ref "U$1") (pin "K2") (pinfunction "DAT0_K2") (pintype "bidirectional"))
    )
    (net (code "80") (name "PC9") (class "Default")
      (node (ref "IC1") (pin "118") (pinfunction "PC9_118") (pintype "bidirectional"))
      (node (ref "U$1") (pin "N2") (pinfunction "DAT1_N2") (pintype "bidirectional"))
    )
    (net (code "81") (name "PC10") (class "Default")
      (node (ref "IC1") (pin "139") (pinfunction "PC10_139") (pintype "bidirectional"))
      (node (ref "U$1") (pin "K3") (pinfunction "DAT2_K3") (pintype "bidirectional"))
    )
    (net (code "82") (name "PC11") (class "Default")
      (node (ref "IC1") (pin "140") (pinfunction "PC11_140") (pintype "bidirectional"))
      (node (ref "U$1") (pin "N3") (pinfunction "DAT3_N3") (pintype "bidirectional"))
    )
    (net (code "83") (name "PC12") (class "Default")
      (node (ref "IC1") (pin "141") (pinfunction "PC12_141") (pintype "bidirectional"))
      (node (ref "U$1") (pin "P6") (pinfunction "CLK_P6") (pintype "bidirectional"))
    )
    (net (code "84") (name "PC13") (class "Default")
      (node (ref "IC1") (pin "8") (pinfunction "PC13_8") (pintype "bidirectional"))
      (node (ref "U1") (pin "23") (pinfunction "XCS_23") (pintype "input"))
    )
    (net (code "85") (name "PC14") (class "Default")
      (node (ref "IC1") (pin "9") (pinfunction "PC14/OSC32_IN_9") (pintype "bidirectional"))
      (node (ref "U1") (pin "13") (pinfunction "XDCS/BSYNC_13") (pintype "input"))
    )
    (net (code "86") (name "PC15") (class "Default")
      (node (ref "IC1") (pin "10") (pinfunction "PC15/OSC32_OUT_10") (pintype "bidirectional"))
      (node (ref "U1") (pin "8") (pinfunction "DREQ_8") (pintype "output"))
    )
    (net (code "87") (name "PD0") (class "Default")
      (node (ref "IC1") (pin "142") (pinfunction "PD0_142") (pintype "bidirectional"))
      (node (ref "U$2") (pin "C7") (pinfunction "DQ2_C7") (pintype "bidirectional"))
    )
    (net (code "88") (name "PD1") (class "Default")
      (node (ref "IC1") (pin "143") (pinfunction "PD1_143") (pintype "bidirectional"))
      (node (ref "U$2") (pin "D7") (pinfunction "DQ3_D7") (pintype "bidirectional"))
    )
    (net (code "89") (name "PD2") (class "Default")
      (node (ref "IC1") (pin "144") (pinfunction "PD2_144") (pintype "bidirectional"))
      (node (ref "U$1") (pin "P5") (pinfunction "CMD_P5") (pintype "bidirectional"))
    )
    (net (code "90") (name "PD3") (class "Default")
      (node (ref "IC1") (pin "145") (pinfunction "PD3_145") (pintype "bidirectional"))
    )
    (net (code "91") (name "PD4") (class "Default")
      (node (ref "IC1") (pin "146") (pinfunction "PD4_146") (pintype "bidirectional"))
    )
    (net (code "92") (name "PD5") (class "Default")
      (node (ref "IC1") (pin "147") (pinfunction "PD5_147") (pintype "bidirectional"))
    )
    (net (code "93") (name "PD6") (class "Default")
      (node (ref "IC1") (pin "150") (pinfunction "PD6_150") (pintype "bidirectional"))
    )
    (net (code "94") (name "PD7") (class "Default")
      (node (ref "IC1") (pin "151") (pinfunction "PD7_151") (pintype "bidirectional"))
    )
    (net (code "95") (name "PD8") (class "Default")
      (node (ref "IC1") (pin "96") (pinfunction "PD8_96") (pintype "bidirectional"))
      (node (ref "U$2") (pin "C1") (pinfunction "DQ13_C1") (pintype "bidirectional"))
    )
    (net (code "96") (name "PD9") (class "Default")
      (node (ref "IC1") (pin "97") (pinfunction "PD9_97") (pintype "bidirectional"))
      (node (ref "U$2") (pin "B1") (pinfunction "DQ14_B1") (pintype "bidirectional"))
    )
    (net (code "97") (name "PD10") (class "Default")
      (node (ref "IC1") (pin "98") (pinfunction "PD10_98") (pintype "bidirectional"))
      (node (ref "U$2") (pin "A2") (pinfunction "DQ15_A2") (pintype "bidirectional"))
    )
    (net (code "98") (name "PD11") (class "Default")
      (node (ref "IC1") (pin "99") (pinfunction "PD11_99") (pintype "bidirectional"))
    )
    (net (code "99") (name "PD12") (class "Default")
      (node (ref "IC1") (pin "100") (pinfunction "PD12_100") (pintype "bidirectional"))
    )
    (net (code "100") (name "PD13") (class "Default")
      (node (ref "IC1") (pin "101") (pinfunction "PD13_101") (pintype "bidirectional"))
    )
    (net (code "101") (name "PD14") (class "Default")
      (node (ref "IC1") (pin "104") (pinfunction "PD14_104") (pintype "bidirectional"))
      (node (ref "U$2") (pin "A6") (pinfunction "DQ0_A6") (pintype "bidirectional"))
    )
    (net (code "102") (name "PD15") (class "Default")
      (node (ref "IC1") (pin "105") (pinfunction "PD15_105") (pintype "bidirectional"))
      (node (ref "U$2") (pin "B7") (pinfunction "DQ1_B7") (pintype "bidirectional"))
    )
    (net (code "103") (name "PDR_ON") (class "Default")
      (node (ref "IC1") (pin "171") (pinfunction "PDR_ON_171") (pintype "power_in"))
    )
    (net (code "104") (name "PE0") (class "Default")
      (node (ref "IC1") (pin "169") (pinfunction "PE0_169") (pintype "bidirectional"))
      (node (ref "U$2") (pin "J6") (pinfunction "LDQM_J6") (pintype "bidirectional"))
    )
    (net (code "105") (name "PE1") (class "Default")
      (node (ref "IC1") (pin "170") (pinfunction "PE1_170") (pintype "bidirectional"))
      (node (ref "U$2") (pin "J2") (pinfunction "UDQM_J2") (pintype "bidirectional"))
    )
    (net (code "106") (name "PE2") (class "Default")
      (node (ref "IC1") (pin "1") (pinfunction "PE2_1") (pintype "bidirectional"))
    )
    (net (code "107") (name "PE3") (class "Default")
      (node (ref "IC1") (pin "2") (pinfunction "PE3_2") (pintype "bidirectional"))
    )
    (net (code "108") (name "PE4") (class "Default")
      (node (ref "IC1") (pin "3") (pinfunction "PE4_3") (pintype "bidirectional"))
    )
    (net (code "109") (name "PE5") (class "Default")
      (node (ref "IC1") (pin "4") (pinfunction "PE5_4") (pintype "bidirectional"))
    )
    (net (code "110") (name "PE6") (class "Default")
      (node (ref "IC1") (pin "5") (pinfunction "PE6_5") (pintype "bidirectional"))
    )
    (net (code "111") (name "PE7") (class "Default")
      (node (ref "IC1") (pin "68") (pinfunction "PE7_68") (pintype "bidirectional"))
      (node (ref "U$2") (pin "D6") (pinfunction "DQ4_D6") (pintype "bidirectional"))
    )
    (net (code "112") (name "PE8") (class "Default")
      (node (ref "IC1") (pin "69") (pinfunction "PE8_69") (pintype "bidirectional"))
      (node (ref "U$2") (pin "E7") (pinfunction "DQ5_E7") (pintype "bidirectional"))
    )
    (net (code "113") (name "PE9") (class "Default")
      (node (ref "IC1") (pin "70") (pinfunction "PE9_70") (pintype "bidirectional"))
      (node (ref "U$2") (pin "F7") (pinfunction "DQ6_F7") (pintype "bidirectional"))
    )
    (net (code "114") (name "PE10") (class "Default")
      (node (ref "IC1") (pin "73") (pinfunction "PE10_73") (pintype "bidirectional"))
      (node (ref "U$2") (pin "G7") (pinfunction "DQ7_G7") (pintype "bidirectional"))
    )
    (net (code "115") (name "PE11") (class "Default")
      (node (ref "IC1") (pin "74") (pinfunction "PE11_74") (pintype "bidirectional"))
      (node (ref "U$2") (pin "G1") (pinfunction "DQ8_G1") (pintype "bidirectional"))
    )
    (net (code "116") (name "PE12") (class "Default")
      (node (ref "IC1") (pin "75") (pinfunction "PE12_75") (pintype "bidirectional"))
      (node (ref "U$2") (pin "F1") (pinfunction "DQ9_F1") (pintype "bidirectional"))
    )
    (net (code "117") (name "PE13") (class "Default")
      (node (ref "IC1") (pin "76") (pinfunction "PE13_76") (pintype "bidirectional"))
      (node (ref "U$2") (pin "E1") (pinfunction "DQ10_E1") (pintype "bidirectional"))
    )
    (net (code "118") (name "PE14") (class "Default")
      (node (ref "IC1") (pin "77") (pinfunction "PE14_77") (pintype "bidirectional"))
      (node (ref "U$2") (pin "D2") (pinfunction "DQ11_D2") (pintype "bidirectional"))
    )
    (net (code "119") (name "PE15") (class "Default")
      (node (ref "IC1") (pin "78") (pinfunction "PE15_78") (pintype "bidirectional"))
      (node (ref "U$2") (pin "D1") (pinfunction "DQ12_D1") (pintype "bidirectional"))
    )
    (net (code "120") (name "PF0") (class "Default")
      (node (ref "IC1") (pin "16") (pinfunction "PF0_16") (pintype "bidirectional"))
      (node (ref "U$2") (pin "N6") (pinfunction "A0_N6") (pintype "bidirectional"))
    )
    (net (code "121") (name "PF1") (class "Default")
      (node (ref "IC1") (pin "17") (pinfunction "PF1_17") (pintype "bidirectional"))
      (node (ref "U$2") (pin "P7") (pinfunction "A1_P7") (pintype "bidirectional"))
    )
    (net (code "122") (name "PF2") (class "Default")
      (node (ref "IC1") (pin "18") (pinfunction "PF2_18") (pintype "bidirectional"))
      (node (ref "U$2") (pin "P6") (pinfunction "A2_P6") (pintype "bidirectional"))
    )
    (net (code "123") (name "PF3") (class "Default")
      (node (ref "IC1") (pin "19") (pinfunction "PF3_19") (pintype "bidirectional"))
      (node (ref "U$2") (pin "R6") (pinfunction "A3_R6") (pintype "bidirectional"))
    )
    (net (code "124") (name "PF4") (class "Default")
      (node (ref "IC1") (pin "20") (pinfunction "PF4_20") (pintype "bidirectional"))
      (node (ref "U$2") (pin "R2") (pinfunction "A4_R2") (pintype "bidirectional"))
    )
    (net (code "125") (name "PF5") (class "Default")
      (node (ref "IC1") (pin "21") (pinfunction "PF5_21") (pintype "bidirectional"))
      (node (ref "U$2") (pin "P2") (pinfunction "A5_P2") (pintype "bidirectional"))
    )
    (net (code "126") (name "PF6") (class "Default")
      (node (ref "IC1") (pin "24") (pinfunction "PF6_24") (pintype "bidirectional"))
    )
    (net (code "127") (name "PF7") (class "Default")
      (node (ref "IC1") (pin "25") (pinfunction "PF7_25") (pintype "bidirectional"))
    )
    (net (code "128") (name "PF8") (class "Default")
      (node (ref "IC1") (pin "26") (pinfunction "PF8_26") (pintype "bidirectional"))
    )
    (net (code "129") (name "PF9") (class "Default")
      (node (ref "IC1") (pin "27") (pinfunction "PF9_27") (pintype "bidirectional"))
    )
    (net (code "130") (name "PF10") (class "Default")
      (node (ref "IC1") (pin "28") (pinfunction "PF10_28") (pintype "bidirectional"))
    )
    (net (code "131") (name "PF11") (class "Default")
      (node (ref "IC1") (pin "59") (pinfunction "PF11_59") (pintype "bidirectional"))
      (node (ref "U$2") (pin "K6") (pinfunction "RAS\\_K6") (pintype "bidirectional"))
    )
    (net (code "132") (name "PF12") (class "Default")
      (node (ref "IC1") (pin "60") (pinfunction "PF12_60") (pintype "bidirectional"))
      (node (ref "U$2") (pin "P1") (pinfunction "A6_P1") (pintype "bidirectional"))
    )
    (net (code "133") (name "PF13") (class "Default")
      (node (ref "IC1") (pin "63") (pinfunction "PF13_63") (pintype "bidirectional"))
      (node (ref "U$2") (pin "N2") (pinfunction "A7_N2") (pintype "bidirectional"))
    )
    (net (code "134") (name "PF14") (class "Default")
      (node (ref "IC1") (pin "64") (pinfunction "PF14_64") (pintype "bidirectional"))
      (node (ref "U$2") (pin "N1") (pinfunction "A8_N1") (pintype "bidirectional"))
    )
    (net (code "135") (name "PF15") (class "Default")
      (node (ref "IC1") (pin "65") (pinfunction "PF15_65") (pintype "bidirectional"))
      (node (ref "U$2") (pin "M2") (pinfunction "A9_M2") (pintype "bidirectional"))
    )
    (net (code "136") (name "PG0") (class "Default")
      (node (ref "IC1") (pin "66") (pinfunction "PG0_66") (pintype "bidirectional"))
      (node (ref "U$2") (pin "N7") (pinfunction "A10_N7") (pintype "bidirectional"))
    )
    (net (code "137") (name "PG1") (class "Default")
      (node (ref "IC1") (pin "67") (pinfunction "PG1_67") (pintype "bidirectional"))
      (node (ref "U$2") (pin "M1") (pinfunction "A11_M1") (pintype "bidirectional"))
    )
    (net (code "138") (name "PG2") (class "Default")
      (node (ref "IC1") (pin "106") (pinfunction "PG2_106") (pintype "bidirectional"))
    )
    (net (code "139") (name "PG3") (class "Default")
      (node (ref "IC1") (pin "107") (pinfunction "PG3_107") (pintype "bidirectional"))
    )
    (net (code "140") (name "PG4") (class "Default")
      (node (ref "IC1") (pin "108") (pinfunction "PG4_108") (pintype "bidirectional"))
      (node (ref "U$2") (pin "M7") (pinfunction "BA0_M7") (pintype "bidirectional"))
    )
    (net (code "141") (name "PG5") (class "Default")
      (node (ref "IC1") (pin "109") (pinfunction "PG5_109") (pintype "bidirectional"))
      (node (ref "U$2") (pin "M6") (pinfunction "BA1_M6") (pintype "bidirectional"))
    )
    (net (code "142") (name "PG6") (class "Default")
      (node (ref "IC1") (pin "110") (pinfunction "PG6_110") (pintype "bidirectional"))
    )
    (net (code "143") (name "PG7") (class "Default")
      (node (ref "IC1") (pin "111") (pinfunction "PG7_111") (pintype "bidirectional"))
    )
    (net (code "144") (name "PG8") (class "Default")
      (node (ref "IC1") (pin "112") (pinfunction "PG8_112") (pintype "bidirectional"))
      (node (ref "U$2") (pin "K2") (pinfunction "CLK_K2") (pintype "bidirectional"))
    )
    (net (code "145") (name "PG9") (class "Default")
      (node (ref "IC1") (pin "152") (pinfunction "PG9_152") (pintype "bidirectional"))
    )
    (net (code "146") (name "PG10") (class "Default")
      (node (ref "IC1") (pin "153") (pinfunction "PG10_153") (pintype "bidirectional"))
    )
    (net (code "147") (name "PG11") (class "Default")
      (node (ref "IC1") (pin "154") (pinfunction "PG11_154") (pintype "bidirectional"))
    )
    (net (code "148") (name "PG12") (class "Default")
      (node (ref "IC1") (pin "155") (pinfunction "PG12_155") (pintype "bidirectional"))
    )
    (net (code "149") (name "PG13") (class "Default")
      (node (ref "IC1") (pin "156") (pinfunction "PG13_156") (pintype "bidirectional"))
    )
    (net (code "150") (name "PG14") (class "Default")
      (node (ref "IC1") (pin "157") (pinfunction "PG14_157") (pintype "bidirectional"))
    )
    (net (code "151") (name "PG15") (class "Default")
      (node (ref "IC1") (pin "160") (pinfunction "PG15_160") (pintype "bidirectional"))
      (node (ref "U$2") (pin "K7") (pinfunction "CAS\\_K7") (pintype "bidirectional"))
    )
    (net (code "152") (name "PH2") (class "Default")
      (node (ref "IC1") (pin "43") (pinfunction "PH2_43") (pintype "bidirectional"))
    )
    (net (code "153") (name "PH3") (class "Default")
      (node (ref "IC1") (pin "44") (pinfunction "PH3_44") (pintype "bidirectional"))
    )
    (net (code "154") (name "PH4") (class "Default")
      (node (ref "IC1") (pin "45") (pinfunction "PH4_45") (pintype "bidirectional"))
    )
    (net (code "155") (name "PH5") (class "Default")
      (node (ref "IC1") (pin "46") (pinfunction "PH5_46") (pintype "bidirectional"))
    )
    (net (code "156") (name "PH6") (class "Default")
      (node (ref "IC1") (pin "83") (pinfunction "PH6_83") (pintype "bidirectional"))
    )
    (net (code "157") (name "PH7") (class "Default")
      (node (ref "IC1") (pin "84") (pinfunction "PH7_84") (pintype "bidirectional"))
    )
    (net (code "158") (name "PH8") (class "Default")
      (node (ref "IC1") (pin "85") (pinfunction "PH8_85") (pintype "bidirectional"))
    )
    (net (code "159") (name "PH9") (class "Default")
      (node (ref "IC1") (pin "86") (pinfunction "PH9_86") (pintype "bidirectional"))
    )
    (net (code "160") (name "PH10") (class "Default")
      (node (ref "IC1") (pin "87") (pinfunction "PH10_87") (pintype "bidirectional"))
    )
    (net (code "161") (name "PH11") (class "Default")
      (node (ref "IC1") (pin "88") (pinfunction "PH11_88") (pintype "bidirectional"))
    )
    (net (code "162") (name "PH12") (class "Default")
      (node (ref "IC1") (pin "89") (pinfunction "PH12_89") (pintype "bidirectional"))
    )
    (net (code "163") (name "PH13") (class "Default")
      (node (ref "IC1") (pin "128") (pinfunction "PH13_128") (pintype "bidirectional"))
    )
    (net (code "164") (name "PH14") (class "Default")
      (node (ref "IC1") (pin "129") (pinfunction "PH14_129") (pintype "bidirectional"))
    )
    (net (code "165") (name "PH15") (class "Default")
      (node (ref "IC1") (pin "130") (pinfunction "PH15_130") (pintype "bidirectional"))
    )
    (net (code "166") (name "PI0") (class "Default")
      (node (ref "IC1") (pin "131") (pinfunction "PI0_131") (pintype "bidirectional"))
    )
    (net (code "167") (name "PI1") (class "Default")
      (node (ref "IC1") (pin "132") (pinfunction "PI1_132") (pintype "bidirectional"))
    )
    (net (code "168") (name "PI2") (class "Default")
      (node (ref "IC1") (pin "133") (pinfunction "PI2_133") (pintype "bidirectional"))
    )
    (net (code "169") (name "PI3") (class "Default")
      (node (ref "IC1") (pin "134") (pinfunction "PI3_134") (pintype "bidirectional"))
    )
    (net (code "170") (name "PI4") (class "Default")
      (node (ref "IC1") (pin "173") (pinfunction "PI4_173") (pintype "bidirectional"))
    )
    (net (code "171") (name "PI5") (class "Default")
      (node (ref "IC1") (pin "174") (pinfunction "PI5_174") (pintype "bidirectional"))
    )
    (net (code "172") (name "PI6") (class "Default")
      (node (ref "IC1") (pin "175") (pinfunction "PI6_175") (pintype "bidirectional"))
    )
    (net (code "173") (name "PI7") (class "Default")
      (node (ref "IC1") (pin "176") (pinfunction "PI7_176") (pintype "bidirectional"))
    )
    (net (code "174") (name "PI8") (class "Default")
      (node (ref "IC1") (pin "7") (pinfunction "PI8_7") (pintype "bidirectional"))
    )
    (net (code "175") (name "PI9") (class "Default")
      (node (ref "IC1") (pin "11") (pinfunction "PI9_11") (pintype "bidirectional"))
    )
    (net (code "176") (name "PI10") (class "Default")
      (node (ref "IC1") (pin "12") (pinfunction "PI10_12") (pintype "bidirectional"))
    )
    (net (code "177") (name "PI11") (class "Default")
      (node (ref "IC1") (pin "13") (pinfunction "PI11_13") (pintype "bidirectional"))
    )
    (net (code "178") (name "SD_CLK") (class "Default")
      (node (ref "IC3") (pin "53") (pinfunction "PC12_53") (pintype "bidirectional"))
    )
    (net (code "179") (name "SD_CMD") (class "Default")
      (node (ref "IC3") (pin "54") (pinfunction "PD2_54") (pintype "bidirectional"))
    )
    (net (code "180") (name "SD_D0") (class "Default")
      (node (ref "IC3") (pin "39") (pinfunction "PC8_39") (pintype "bidirectional"))
    )
    (net (code "181") (name "SD_D1") (class "Default")
      (node (ref "IC3") (pin "40") (pinfunction "PC9_40") (pintype "bidirectional"))
    )
    (net (code "182") (name "SD_D2") (class "Default")
      (node (ref "IC3") (pin "51") (pinfunction "PC10_51") (pintype "bidirectional"))
    )
    (net (code "183") (name "SD_D3") (class "Default")
      (node (ref "IC3") (pin "52") (pinfunction "PC11_52") (pintype "bidirectional"))
    )
    (net (code "184") (name "SPI_MISO") (class "Default")
      (node (ref "IC3") (pin "22") (pinfunction "PA6_22") (pintype "bidirectional"))
    )
    (net (code "185") (name "SPI_MOSI") (class "Default")
      (node (ref "IC3") (pin "23") (pinfunction "PA7_23") (pintype "bidirectional"))
    )
    (net (code "186") (name "SPI_SCK") (class "Default")
      (node (ref "IC3") (pin "55") (pinfunction "PB3_55") (pintype "bidirectional"))
    )
    (net (code "187") (name "SPI_SSEL") (class "Default")
      (node (ref "IC3") (pin "50") (pinfunction "PA15_50") (pintype "bidirectional"))
    )
    (net (code "188") (name "SWCLK") (class "Default")
      (node (ref "IC3") (pin "49") (pinfunction "PA14_49") (pintype "bidirectional"))
    )
    (net (code "189") (name "SWDIO") (class "Default")
      (node (ref "IC3") (pin "46") (pinfunction "PA13_46") (pintype "bidirectional"))
    )
    (net (code "190") (name "ULPI_CK") (class "Default")
      (node (ref "IC2") (pin "27") (pinfunction "CLOCK_27") (pintype "bidirectional"))
      (node (ref "IC3") (pin "21") (pinfunction "PA5_21") (pintype "bidirectional"))
    )
    (net (code "191") (name "ULPI_D0") (class "Default")
      (node (ref "IC2") (pin "2") (pinfunction "D0_2") (pintype "bidirectional"))
      (node (ref "IC3") (pin "17") (pinfunction "PA3_17") (pintype "bidirectional"))
    )
    (net (code "192") (name "ULPI_D1") (class "Default")
      (node (ref "IC2") (pin "1") (pinfunction "D1_1") (pintype "bidirectional"))
      (node (ref "IC3") (pin "26") (pinfunction "PB0_26") (pintype "bidirectional"))
    )
    (net (code "193") (name "ULPI_D2") (class "Default")
      (node (ref "IC2") (pin "32") (pinfunction "D2_32") (pintype "bidirectional"))
      (node (ref "IC3") (pin "27") (pinfunction "PB1_27") (pintype "bidirectional"))
    )
    (net (code "194") (name "ULPI_D3") (class "Default")
      (node (ref "IC2") (pin "30") (pinfunction "D3_30") (pintype "bidirectional"))
      (node (ref "IC3") (pin "29") (pinfunction "PB10_29") (pintype "bidirectional"))
    )
    (net (code "195") (name "ULPI_D4") (class "Default")
      (node (ref "IC2") (pin "26") (pinfunction "D4_26") (pintype "bidirectional"))
      (node (ref "IC3") (pin "30") (pinfunction "PB11_30") (pintype "bidirectional"))
    )
    (net (code "196") (name "ULPI_D5") (class "Default")
      (node (ref "IC2") (pin "25") (pinfunction "D5_25") (pintype "bidirectional"))
      (node (ref "IC3") (pin "33") (pinfunction "PB12_33") (pintype "bidirectional"))
    )
    (net (code "197") (name "ULPI_D6") (class "Default")
      (node (ref "IC2") (pin "24") (pinfunction "D6_24") (pintype "bidirectional"))
      (node (ref "IC3") (pin "34") (pinfunction "PB13_34") (pintype "bidirectional"))
    )
    (net (code "198") (name "ULPI_D7") (class "Default")
      (node (ref "IC2") (pin "23") (pinfunction "D7_23") (pintype "bidirectional"))
      (node (ref "IC3") (pin "57") (pinfunction "PB5_57") (pintype "bidirectional"))
    )
    (net (code "199") (name "ULPI_DIR") (class "Default")
      (node (ref "IC2") (pin "18") (pinfunction "DIR_18") (pintype "bidirectional"))
      (node (ref "IC3") (pin "10") (pinfunction "PC2_10") (pintype "bidirectional"))
    )
    (net (code "200") (name "ULPI_NXT") (class "Default")
      (node (ref "IC2") (pin "22") (pinfunction "NXT_22") (pintype "bidirectional"))
      (node (ref "IC3") (pin "11") (pinfunction "PC3_11") (pintype "bidirectional"))
    )
    (net (code "201") (name "ULPI_STP") (class "Default")
      (node (ref "IC2") (pin "21") (pinfunction "STP_21") (pintype "bidirectional"))
      (node (ref "IC3") (pin "8") (pinfunction "PC0_8") (pintype "bidirectional"))
    )
    (net (code "202") (name "VCAP_1") (class "Default")
      (node (ref "IC1") (pin "81") (pinfunction "VCAP_1_81") (pintype "power_in"))
    )
    (net (code "203") (name "VCAP_2") (class "Default")
      (node (ref "IC1") (pin "125") (pinfunction "VCAP_2_125") (pintype "power_in"))
    )
    (net (code "204") (name "VDD") (class "Default")
      (node (ref "IC1") (pin "103") (pinfunction "VDD_103") (pintype "power_in"))
      (node (ref "IC1") (pin "114") (pinfunction "VDD_114") (pintype "power_in"))
      (node (ref "IC1") (pin "127") (pinfunction "VDD_127") (pintype "power_in"))
      (node (ref "IC1") (pin "136") (pinfunction "VDD_136") (pintype "power_in"))
      (node (ref "IC1") (pin "149") (pinfunction "VDD_149") (pintype "power_in"))
      (node (ref "IC1") (pin "15") (pinfunction "VDD_15") (pintype "power_in"))
      (node (ref "IC1") (pin "159") (pinfunction "VDD_159") (pintype "power_in"))
      (node (ref "IC1") (pin "172") (pinfunction "VDD_172") (pintype "power_in"))
      (node (ref "IC1") (pin "23") (pinfunction "VDD_23") (pintype "power_in"))
      (node (ref "IC1") (pin "36") (pinfunction "VDD_36") (pintype "power_in"))
      (node (ref "IC1") (pin "39") (pinfunction "VDDA_39") (pintype "power_in"))
      (node (ref "IC1") (pin "49") (pinfunction "VDD_49") (pintype "power_in"))
      (node (ref "IC1") (pin "6") (pinfunction "VBAT_6") (pintype "power_in"))
      (node (ref "IC1") (pin "62") (pinfunction "VDD_62") (pintype "bidirectional"))
      (node (ref "IC1") (pin "72") (pinfunction "VDD_72") (pintype "power_in"))
      (node (ref "IC1") (pin "82") (pinfunction "VDD_82") (pintype "power_in"))
      (node (ref "IC1") (pin "91") (pinfunction "VDD_91") (pintype "power_in"))
      (node (ref "U$1") (pin "E4") (pinfunction "VDDIM_E4") (pintype "bidirectional"))
      (node (ref "U$1") (pin "F2") (pinfunction "VCC_F2") (pintype "bidirectional"))
      (node (ref "U$1") (pin "F3") (pinfunction "VCC_F3") (pintype "bidirectional"))
      (node (ref "U$1") (pin "F4") (pinfunction "VCC_F4") (pintype "bidirectional"))
      (node (ref "U$1") (pin "F5") (pinfunction "VCC_F5") (pintype "bidirectional"))
      (node (ref "U$1") (pin "F6") (pinfunction "VCC_F6") (pintype "bidirectional"))
      (node (ref "U$1") (pin "F7") (pinfunction "VCC_F7") (pintype "bidirectional"))
      (node (ref "U$1") (pin "F8") (pinfunction "VCC_F8") (pintype "bidirectional"))
      (node (ref "U$1") (pin "F9") (pinfunction "VCC_F9") (pintype "bidirectional"))
      (node (ref "U$1") (pin "H3") (pinfunction "VCCQ_H3") (pintype "bidirectional"))
      (node (ref "U$1") (pin "H8") (pinfunction "VCCQ_H8") (pintype "bidirectional"))
      (node (ref "U$1") (pin "L2") (pinfunction "VCCQ_L2") (pintype "bidirectional"))
      (node (ref "U$1") (pin "L4") (pinfunction "VCCQ_L4") (pintype "bidirectional"))
      (node (ref "U$1") (pin "L7") (pinfunction "VCCQ_L7") (pintype "bidirectional"))
      (node (ref "U$1") (pin "L9") (pinfunction "VCCQ_L9") (pintype "bidirectional"))
      (node (ref "U$1") (pin "P3") (pinfunction "VCCQ_P3") (pintype "bidirectional"))
      (node (ref "U$1") (pin "P8") (pinfunction "VCCQ_P8") (pintype "bidirectional"))
      (node (ref "U$10") (pin "P$2") (pinfunction "P$2_P$2") (pintype "bidirectional"))
      (node (ref "U$11") (pin "P$2") (pinfunction "P$2_P$2") (pintype "bidirectional"))
      (node (ref "U$12") (pin "P$2") (pinfunction "P$2_P$2") (pintype "bidirectional"))
      (node (ref "U$13") (pin "P$2") (pinfunction "P$2_P$2") (pintype "bidirectional"))
      (node (ref "U$14") (pin "P$2") (pinfunction "P$2_P$2") (pintype "bidirectional"))
      (node (ref "U$15") (pin "P$2") (pinfunction "P$2_P$2") (pintype "bidirectional"))
      (node (ref "U$16") (pin "P$2") (pinfunction "P$2_P$2") (pintype "bidirectional"))
      (node (ref "U$17") (pin "P$2") (pinfunction "P$2_P$2") (pintype "bidirectional"))
      (node (ref "U$18") (pin "P$2") (pinfunction "P$2_P$2") (pintype "bidirectional"))
      (node (ref "U$19") (pin "P$2") (pinfunction "P$2_P$2") (pintype "bidirectional"))
      (node (ref "U$2") (pin "A7") (pinfunction "VDD_A7") (pintype "bidirectional"))
      (node (ref "U$2") (pin "B6") (pinfunction "VDDQ_B6") (pintype "bidirectional"))
      (node (ref "U$2") (pin "C2") (pinfunction "VDDQ_C2") (pintype "bidirectional"))
      (node (ref "U$2") (pin "E6") (pinfunction "VDDQ_E6") (pintype "bidirectional"))
      (node (ref "U$2") (pin "F2") (pinfunction "VDDQ_F2") (pintype "bidirectional"))
      (node (ref "U$2") (pin "H6") (pinfunction "VDD_H6") (pintype "bidirectional"))
      (node (ref "U$2") (pin "R7") (pinfunction "VDD_R7") (pintype "bidirectional"))
      (node (ref "U$22") (pin "P$2") (pinfunction "P$2_P$2") (pintype "bidirectional"))
      (node (ref "U$23") (pin "P$2") (pinfunction "P$2_P$2") (pintype "bidirectional"))
      (node (ref "U$24") (pin "P$2") (pinfunction "P$2_P$2") (pintype "bidirectional"))
      (node (ref "U$25") (pin "P$2") (pinfunction "P$2_P$2") (pintype "bidirectional"))
      (node (ref "U$26") (pin "P$2") (pinfunction "P$2_P$2") (pintype "bidirectional"))
      (node (ref "U$27") (pin "P$2") (pinfunction "P$2_P$2") (pintype "bidirectional"))
      (node (ref "U$28") (pin "P$2") (pinfunction "P$2_P$2") (pintype "bidirectional"))
      (node (ref "U$29") (pin "P$2") (pinfunction "P$2_P$2") (pintype "bidirectional"))
      (node (ref "U$3") (pin "P$2") (pinfunction "P$2_P$2") (pintype "bidirectional"))
      (node (ref "U$30") (pin "P$2") (pinfunction "P$2_P$2") (pintype "bidirectional"))
      (node (ref "U$31") (pin "P$2") (pinfunction "P$2_P$2") (pintype "bidirectional"))
      (node (ref "U$32") (pin "P$2") (pinfunction "P$2_P$2") (pintype "bidirectional"))
      (node (ref "U$33") (pin "P$2") (pinfunction "P$2_P$2") (pintype "bidirectional"))
      (node (ref "U$34") (pin "P$2") (pinfunction "P$2_P$2") (pintype "bidirectional"))
      (node (ref "U$35") (pin "P$2") (pinfunction "P$2_P$2") (pintype "bidirectional"))
      (node (ref "U$36") (pin "P$2") (pinfunction "P$2_P$2") (pintype "bidirectional"))
      (node (ref "U$37") (pin "P$2") (pinfunction "P$2_P$2") (pintype "bidirectional"))
      (node (ref "U$38") (pin "P$2") (pinfunction "P$2_P$2") (pintype "bidirectional"))
      (node (ref "U$39") (pin "P$2") (pinfunction "P$2_P$2") (pintype "bidirectional"))
      (node (ref "U$4") (pin "P$2") (pinfunction "P$2_P$2") (pintype "bidirectional"))
      (node (ref "U$40") (pin "P$2") (pinfunction "P$2_P$2") (pintype "bidirectional"))
      (node (ref "U$41") (pin "P$2") (pinfunction "P$2_P$2") (pintype "bidirectional"))
      (node (ref "U$42") (pin "P$2") (pinfunction "P$2_P$2") (pintype "bidirectional"))
      (node (ref "U$43") (pin "P$2") (pinfunction "P$2_P$2") (pintype "bidirectional"))
      (node (ref "U$44") (pin "P$2") (pinfunction "P$2_P$2") (pintype "bidirectional"))
      (node (ref "U$45") (pin "P$2") (pinfunction "P$2_P$2") (pintype "bidirectional"))
      (node (ref "U$5") (pin "P$2") (pinfunction "P$2_P$2") (pintype "bidirectional"))
      (node (ref "U$6") (pin "P$2") (pinfunction "P$2_P$2") (pintype "bidirectional"))
      (node (ref "U$7") (pin "P$2") (pinfunction "P$2_P$2") (pintype "bidirectional"))
      (node (ref "U$8") (pin "P$2") (pinfunction "P$2_P$2") (pintype "bidirectional"))
      (node (ref "U$9") (pin "P$2") (pinfunction "P$2_P$2") (pintype "bidirectional"))
    )
    (net (code "205") (name "VREF+") (class "Default")
      (node (ref "IC1") (pin "38") (pinfunction "VREF+_38") (pintype "power_in"))
    )
    (net (code "206") (name "VS_DATA") (class "Default")
      (node (ref "U1") (pin "12") (pinfunction "GPIO7/I2S_DATA_12") (pintype "bidirectional"))
    )
    (net (code "207") (name "VS_DCLK") (class "Default")
      (node (ref "U1") (pin "9") (pinfunction "GPIO2/DCLK_9") (pintype "bidirectional"))
    )
    (net (code "208") (name "VS_LROUT") (class "Default")
      (node (ref "U1") (pin "36") (pinfunction "GPIO4/I2S_LROUT_36") (pintype "bidirectional"))
    )
    (net (code "209") (name "VS_MCLK") (class "Default")
      (node (ref "U1") (pin "25") (pinfunction "GPIO5/I2S_MCLK_25") (pintype "bidirectional"))
    )
    (net (code "210") (name "VS_SCLK") (class "Default")
      (node (ref "U1") (pin "11") (pinfunction "GPIO6/I2S_SCLK_11") (pintype "bidirectional"))
    )
    (net (code "211") (name "VS_SDATA") (class "Default")
      (node (ref "U1") (pin "10") (pinfunction "GPIO3/SDATA_10") (pintype "bidirectional"))
    )
    (net (code "212") (name "WAKEUP") (class "Default")
      (node (ref "IC3") (pin "14") (pinfunction "PA0_14") (pintype "bidirectional"))
    )
    (net (code "213") (name "unconnected-(IC1-BOOT0-Pad166)") (class "Default")
      (node (ref "IC1") (pin "166") (pinfunction "BOOT0_166") (pintype "input"))
    )
    (net (code "214") (name "unconnected-(IC1-BYPASS_REG-Pad48)") (class "Default")
      (node (ref "IC1") (pin "48") (pinfunction "BYPASS_REG_48") (pintype "input"))
    )
    (net (code "215") (name "unconnected-(IC1-NRST-Pad31)") (class "Default")
      (node (ref "IC1") (pin "31") (pinfunction "NRST_31") (pintype "bidirectional"))
    )
    (net (code "216") (name "unconnected-(IC2-CGF1-Pad28)") (class "Default")
      (node (ref "IC2") (pin "28") (pinfunction "CGF1_28") (pintype "bidirectional"))
    )
    (net (code "217") (name "unconnected-(IC2-CLKIN-Pad15)") (class "Default")
      (node (ref "IC2") (pin "15") (pinfunction "CLKIN_15") (pintype "bidirectional"))
    )
    (net (code "218") (name "unconnected-(IC2-DM-Pad4)") (class "Default")
      (node (ref "IC2") (pin "4") (pinfunction "DM_4") (pintype "bidirectional"))
    )
    (net (code "219") (name "unconnected-(IC2-DP-Pad6)") (class "Default")
      (node (ref "IC2") (pin "6") (pinfunction "DP_6") (pintype "bidirectional"))
    )
    (net (code "220") (name "unconnected-(IC2-FAULT-Pad11)") (class "Default")
      (node (ref "IC2") (pin "11") (pinfunction "FAULT_11") (pintype "bidirectional"))
    )
    (net (code "221") (name "unconnected-(IC2-GND-PadEXP)") (class "Default")
      (node (ref "IC2") (pin "EXP") (pinfunction "GND_EXP") (pintype "bidirectional"))
    )
    (net (code "222") (name "unconnected-(IC2-ID-Pad8)") (class "Default")
      (node (ref "IC2") (pin "8") (pinfunction "ID_8") (pintype "bidirectional"))
    )
    (net (code "223") (name "unconnected-(IC2-NC-Pad16)") (class "Default")
      (node (ref "IC2") (pin "16") (pinfunction "NC_16") (pintype "bidirectional"))
    )
    (net (code "224") (name "unconnected-(IC2-PSW-Pad14)") (class "Default")
      (node (ref "IC2") (pin "14") (pinfunction "PSW_14") (pintype "bidirectional"))
    )
    (net (code "225") (name "unconnected-(IC2-RREF-Pad5)") (class "Default")
      (node (ref "IC2") (pin "5") (pinfunction "RREF_5") (pintype "bidirectional"))
    )
    (net (code "226") (name "unconnected-(IC2-TEST-Pad10)") (class "Default")
      (node (ref "IC2") (pin "10") (pinfunction "TEST_10") (pintype "bidirectional"))
    )
    (net (code "227") (name "unconnected-(IC2-VBUS-Pad13)") (class "Default")
      (node (ref "IC2") (pin "13") (pinfunction "VBUS_13") (pintype "bidirectional"))
    )
    (net (code "228") (name "unconnected-(IC2-VCC(3V3)-Pad12)") (class "Default")
      (node (ref "IC2") (pin "12") (pinfunction "VCC(3V3)_12") (pintype "bidirectional"))
    )
    (net (code "229") (name "unconnected-(IC2-VDD(1V2)-Pad17)") (class "Default")
      (node (ref "IC2") (pin "17") (pinfunction "VDD(1V2)_17") (pintype "bidirectional"))
    )
    (net (code "230") (name "unconnected-(IC3-BOOT0-Pad60)") (class "Default")
      (node (ref "IC3") (pin "60") (pinfunction "BOOT0_60") (pintype "bidirectional"))
    )
    (net (code "231") (name "unconnected-(IC3-NRST-Pad7)") (class "Default")
      (node (ref "IC3") (pin "7") (pinfunction "NRST_7") (pintype "bidirectional"))
    )
    (net (code "232") (name "unconnected-(IC3-PC4-Pad24)") (class "Default")
      (node (ref "IC3") (pin "24") (pinfunction "PC4_24") (pintype "bidirectional"))
    )
    (net (code "233") (name "unconnected-(IC3-PC5-Pad25)") (class "Default")
      (node (ref "IC3") (pin "25") (pinfunction "PC5_25") (pintype "bidirectional"))
    )
    (net (code "234") (name "unconnected-(IC3-PC6-Pad37)") (class "Default")
      (node (ref "IC3") (pin "37") (pinfunction "PC6_37") (pintype "bidirectional"))
    )
    (net (code "235") (name "unconnected-(IC3-PC7-Pad38)") (class "Default")
      (node (ref "IC3") (pin "38") (pinfunction "PC7_38") (pintype "bidirectional"))
    )
    (net (code "236") (name "unconnected-(IC3-PC13-Pad2)") (class "Default")
      (node (ref "IC3") (pin "2") (pinfunction "PC13_2") (pintype "bidirectional"))
    )
    (net (code "237") (name "unconnected-(IC3-PH0-Pad5)") (class "Default")
      (node (ref "IC3") (pin "5") (pinfunction "PH0_5") (pintype "bidirectional"))
    )
    (net (code "238") (name "unconnected-(IC3-PH1-Pad6)") (class "Default")
      (node (ref "IC3") (pin "6") (pinfunction "PH1_6") (pintype "bidirectional"))
    )
    (net (code "239") (name "unconnected-(IC3-VBAT-Pad1)") (class "Default")
      (node (ref "IC3") (pin "1") (pinfunction "VBAT_1") (pintype "bidirectional"))
    )
    (net (code "240") (name "unconnected-(IC3-VCAP_1-Pad31)") (class "Default")
      (node (ref "IC3") (pin "31") (pinfunction "VCAP_1_31") (pintype "bidirectional"))
    )
    (net (code "241") (name "unconnected-(IC3-VCAP_2-Pad47)") (class "Default")
      (node (ref "IC3") (pin "47") (pinfunction "VCAP_2_47") (pintype "bidirectional"))
    )
    (net (code "242") (name "unconnected-(IC3-VDD1-Pad19)") (class "Default")
      (node (ref "IC3") (pin "19") (pinfunction "VDD1_19") (pintype "bidirectional"))
    )
    (net (code "243") (name "unconnected-(IC3-VDD2-Pad32)") (class "Default")
      (node (ref "IC3") (pin "32") (pinfunction "VDD2_32") (pintype "bidirectional"))
    )
    (net (code "244") (name "unconnected-(IC3-VDD3-Pad48)") (class "Default")
      (node (ref "IC3") (pin "48") (pinfunction "VDD3_48") (pintype "bidirectional"))
    )
    (net (code "245") (name "unconnected-(IC3-VDD4-Pad64)") (class "Default")
      (node (ref "IC3") (pin "64") (pinfunction "VDD4_64") (pintype "bidirectional"))
    )
    (net (code "246") (name "unconnected-(IC3-VDDA-Pad13)") (class "Default")
      (node (ref "IC3") (pin "13") (pinfunction "VDDA_13") (pintype "bidirectional"))
    )
    (net (code "247") (name "unconnected-(IC3-VSS1-Pad18)") (class "Default")
      (node (ref "IC3") (pin "18") (pinfunction "VSS1_18") (pintype "bidirectional"))
    )
    (net (code "248") (name "unconnected-(IC3-VSS2-Pad63)") (class "Default")
      (node (ref "IC3") (pin "63") (pinfunction "VSS2_63") (pintype "bidirectional"))
    )
    (net (code "249") (name "unconnected-(IC3-VSSA-Pad12)") (class "Default")
      (node (ref "IC3") (pin "12") (pinfunction "VSSA_12") (pintype "bidirectional"))
    )
    (net (code "250") (name "unconnected-(U$1B-NC-PadA1)") (class "Default")
      (node (ref "U$1") (pin "A1") (pinfunction "NC_A1") (pintype "bidirectional"))
    )
    (net (code "251") (name "unconnected-(U$1B-NC-PadA2)") (class "Default")
      (node (ref "U$1") (pin "A2") (pinfunction "NC_A2") (pintype "bidirectional"))
    )
    (net (code "252") (name "unconnected-(U$1B-NC-PadA9)") (class "Default")
      (node (ref "U$1") (pin "A9") (pinfunction "NC_A9") (pintype "bidirectional"))
    )
    (net (code "253") (name "unconnected-(U$1B-NC-PadA10)") (class "Default")
      (node (ref "U$1") (pin "A10") (pinfunction "NC_A10") (pintype "bidirectional"))
    )
    (net (code "254") (name "unconnected-(U$1B-NC-PadB1)") (class "Default")
      (node (ref "U$1") (pin "B1") (pinfunction "NC_B1") (pintype "bidirectional"))
    )
    (net (code "255") (name "unconnected-(U$1B-NC-PadB10)") (class "Default")
      (node (ref "U$1") (pin "B10") (pinfunction "NC_B10") (pintype "bidirectional"))
    )
    (net (code "256") (name "unconnected-(U$1B-NC-PadT1)") (class "Default")
      (node (ref "U$1") (pin "T1") (pinfunction "NC_T1") (pintype "bidirectional"))
    )
    (net (code "257") (name "unconnected-(U$1B-NC-PadT10)") (class "Default")
      (node (ref "U$1") (pin "T10") (pinfunction "NC_T10") (pintype "bidirectional"))
    )
    (net (code "258") (name "unconnected-(U$1B-NC-PadU1)") (class "Default")
      (node (ref "U$1") (pin "U1") (pinfunction "NC_U1") (pintype "bidirectional"))
    )
    (net (code "259") (name "unconnected-(U$1B-NC-PadU2)") (class "Default")
      (node (ref "U$1") (pin "U2") (pinfunction "NC_U2") (pintype "bidirectional"))
    )
    (net (code "260") (name "unconnected-(U$1B-NC-PadU9)") (class "Default")
      (node (ref "U$1") (pin "U9") (pinfunction "NC_U9") (pintype "bidirectional"))
    )
    (net (code "261") (name "unconnected-(U$1B-NC-PadU10)") (class "Default")
      (node (ref "U$1") (pin "U10") (pinfunction "NC_U10") (pintype "bidirectional"))
    )
    (net (code "262") (name "unconnected-(U$1D-RFU-PadD2)") (class "Default")
      (node (ref "U$1") (pin "D2") (pinfunction "RFU_D2") (pintype "bidirectional"))
    )
    (net (code "263") (name "unconnected-(U$1D-RFU-PadD3)") (class "Default")
      (node (ref "U$1") (pin "D3") (pinfunction "RFU_D3") (pintype "bidirectional"))
    )
    (net (code "264") (name "unconnected-(U$1D-RFU-PadD4)") (class "Default")
      (node (ref "U$1") (pin "D4") (pinfunction "RFU_D4") (pintype "bidirectional"))
    )
    (net (code "265") (name "unconnected-(U$1D-RFU-PadD5)") (class "Default")
      (node (ref "U$1") (pin "D5") (pinfunction "RFU_D5") (pintype "bidirectional"))
    )
    (net (code "266") (name "unconnected-(U$1D-RFU-PadD6)") (class "Default")
      (node (ref "U$1") (pin "D6") (pinfunction "RFU_D6") (pintype "bidirectional"))
    )
    (net (code "267") (name "unconnected-(U$1D-RFU-PadD7)") (class "Default")
      (node (ref "U$1") (pin "D7") (pinfunction "RFU_D7") (pintype "bidirectional"))
    )
    (net (code "268") (name "unconnected-(U$1D-RFU-PadD8)") (class "Default")
      (node (ref "U$1") (pin "D8") (pinfunction "RFU_D8") (pintype "bidirectional"))
    )
    (net (code "269") (name "unconnected-(U$1D-RFU-PadD9)") (class "Default")
      (node (ref "U$1") (pin "D9") (pinfunction "RFU_D9") (pintype "bidirectional"))
    )
    (net (code "270") (name "unconnected-(U$1D-RFU-PadE2)") (class "Default")
      (node (ref "U$1") (pin "E2") (pinfunction "RFU_E2") (pintype "bidirectional"))
    )
    (net (code "271") (name "unconnected-(U$1D-RFU-PadE3)") (class "Default")
      (node (ref "U$1") (pin "E3") (pinfunction "RFU_E3") (pintype "bidirectional"))
    )
    (net (code "272") (name "unconnected-(U$1D-RFU-PadE5)") (class "Default")
      (node (ref "U$1") (pin "E5") (pinfunction "RFU_E5") (pintype "bidirectional"))
    )
    (net (code "273") (name "unconnected-(U$1D-RFU-PadE6)") (class "Default")
      (node (ref "U$1") (pin "E6") (pinfunction "RFU_E6") (pintype "bidirectional"))
    )
    (net (code "274") (name "unconnected-(U$1D-RFU-PadE7)") (class "Default")
      (node (ref "U$1") (pin "E7") (pinfunction "RFU_E7") (pintype "bidirectional"))
    )
    (net (code "275") (name "unconnected-(U$1D-RFU-PadE8)") (class "Default")
      (node (ref "U$1") (pin "E8") (pinfunction "RFU_E8") (pintype "bidirectional"))
    )
    (net (code "276") (name "unconnected-(U$1D-RFU-PadE9)") (class "Default")
      (node (ref "U$1") (pin "E9") (pinfunction "RFU_E9") (pintype "bidirectional"))
    )
    (net (code "277") (name "unconnected-(U$1D-RFU-PadH4)") (class "Default")
      (node (ref "U$1") (pin "H4") (pinfunction "RFU_H4") (pintype "bidirectional"))
    )
    (net (code "278") (name "unconnected-(U$1D-RFU-PadH5)") (class "Default")
      (node (ref "U$1") (pin "H5") (pinfunction "RFU_H5") (pintype "bidirectional"))
    )
    (net (code "279") (name "unconnected-(U$1D-RFU-PadH6)") (class "Default")
      (node (ref "U$1") (pin "H6") (pinfunction "RFU_H6") (pintype "bidirectional"))
    )
    (net (code "280") (name "unconnected-(U$1D-RFU-PadH7)") (class "Default")
      (node (ref "U$1") (pin "H7") (pinfunction "RFU_H7") (pintype "bidirectional"))
    )
    (net (code "281") (name "unconnected-(U$1D-RFU-PadJ2)") (class "Default")
      (node (ref "U$1") (pin "J2") (pinfunction "RFU_J2") (pintype "bidirectional"))
    )
    (net (code "282") (name "unconnected-(U$1D-RFU-PadJ3)") (class "Default")
      (node (ref "U$1") (pin "J3") (pinfunction "RFU_J3") (pintype "bidirectional"))
    )
    (net (code "283") (name "unconnected-(U$1D-RFU-PadJ4)") (class "Default")
      (node (ref "U$1") (pin "J4") (pinfunction "RFU_J4") (pintype "bidirectional"))
    )
    (net (code "284") (name "unconnected-(U$1D-RFU-PadJ5)") (class "Default")
      (node (ref "U$1") (pin "J5") (pinfunction "RFU_J5") (pintype "bidirectional"))
    )
    (net (code "285") (name "unconnected-(U$1D-RFU-PadJ6)") (class "Default")
      (node (ref "U$1") (pin "J6") (pinfunction "RFU_J6") (pintype "bidirectional"))
    )
    (net (code "286") (name "unconnected-(U$1D-RFU-PadJ7)") (class "Default")
      (node (ref "U$1") (pin "J7") (pinfunction "RFU_J7") (pintype "bidirectional"))
    )
    (net (code "287") (name "unconnected-(U$1D-RFU-PadJ8)") (class "Default")
      (node (ref "U$1") (pin "J8") (pinfunction "RFU_J8") (pintype "bidirectional"))
    )
    (net (code "288") (name "unconnected-(U$1D-RFU-PadJ9)") (class "Default")
      (node (ref "U$1") (pin "J9") (pinfunction "RFU_J9") (pintype "bidirectional"))
    )
    (net (code "289") (name "unconnected-(U$1D-RFU-PadK4)") (class "Default")
      (node (ref "U$1") (pin "K4") (pinfunction "RFU_K4") (pintype "bidirectional"))
    )
    (net (code "290") (name "unconnected-(U$1D-RFU-PadK5)") (class "Default")
      (node (ref "U$1") (pin "K5") (pinfunction "RFU_K5") (pintype "bidirectional"))
    )
    (net (code "291") (name "unconnected-(U$1D-RFU-PadK6)") (class "Default")
      (node (ref "U$1") (pin "K6") (pinfunction "RFU_K6") (pintype "bidirectional"))
    )
    (net (code "292") (name "unconnected-(U$1D-RFU-PadK7)") (class "Default")
      (node (ref "U$1") (pin "K7") (pinfunction "RFU_K7") (pintype "bidirectional"))
    )
    (net (code "293") (name "unconnected-(U$1D-RFU-PadL5)") (class "Default")
      (node (ref "U$1") (pin "L5") (pinfunction "RFU_L5") (pintype "bidirectional"))
    )
    (net (code "294") (name "unconnected-(U$1D-RFU-PadL6)") (class "Default")
      (node (ref "U$1") (pin "L6") (pinfunction "RFU_L6") (pintype "bidirectional"))
    )
    (net (code "295") (name "unconnected-(U$1D-RFU-PadM2)") (class "Default")
      (node (ref "U$1") (pin "M2") (pinfunction "RFU_M2") (pintype "bidirectional"))
    )
    (net (code "296") (name "unconnected-(U$1D-RFU-PadM3)") (class "Default")
      (node (ref "U$1") (pin "M3") (pinfunction "RFU_M3") (pintype "bidirectional"))
    )
    (net (code "297") (name "unconnected-(U$1D-RFU-PadM6)") (class "Default")
      (node (ref "U$1") (pin "M6") (pinfunction "RFU_M6") (pintype "bidirectional"))
    )
    (net (code "298") (name "unconnected-(U$1D-RFU-PadM8)") (class "Default")
      (node (ref "U$1") (pin "M8") (pinfunction "RFU_M8") (pintype "bidirectional"))
    )
    (net (code "299") (name "unconnected-(U$1D-RFU-PadM9)") (class "Default")
      (node (ref "U$1") (pin "M9") (pinfunction "RFU_M9") (pintype "bidirectional"))
    )
    (net (code "300") (name "unconnected-(U$1D-RFU-PadN4)") (class "Default")
      (node (ref "U$1") (pin "N4") (pinfunction "RFU_N4") (pintype "bidirectional"))
    )
    (net (code "301") (name "unconnected-(U$1D-RFU-PadN5)") (class "Default")
      (node (ref "U$1") (pin "N5") (pinfunction "RFU_N5") (pintype "bidirectional"))
    )
    (net (code "302") (name "unconnected-(U$1D-RFU-PadN6)") (class "Default")
      (node (ref "U$1") (pin "N6") (pinfunction "RFU_N6") (pintype "bidirectional"))
    )
    (net (code "303") (name "unconnected-(U$1D-RFU-PadN7)") (class "Default")
      (node (ref "U$1") (pin "N7") (pinfunction "RFU_N7") (pintype "bidirectional"))
    )
    (net (code "304") (name "unconnected-(U$1D-RFU-PadP4)") (class "Default")
      (node (ref "U$1") (pin "P4") (pinfunction "RFU_P4") (pintype "bidirectional"))
    )
    (net (code "305") (name "unconnected-(U$1D-RFU-PadP7)") (class "Default")
      (node (ref "U$1") (pin "P7") (pinfunction "RFU_P7") (pintype "bidirectional"))
    )
    (net (code "306") (name "unconnected-(U$2-NC-PadG2)") (class "Default")
      (node (ref "U$2") (pin "G2") (pinfunction "NC_G2") (pintype "bidirectional"))
    )
    (net (code "307") (name "unconnected-(U$2-NC-PadG6)") (class "Default")
      (node (ref "U$2") (pin "G6") (pinfunction "NC_G6") (pintype "bidirectional"))
    )
    (net (code "308") (name "unconnected-(U$2-NC-PadH1)") (class "Default")
      (node (ref "U$2") (pin "H1") (pinfunction "NC_H1") (pintype "bidirectional"))
    )
    (net (code "309") (name "unconnected-(U$2-NC-PadH2)") (class "Default")
      (node (ref "U$2") (pin "H2") (pinfunction "NC_H2") (pintype "bidirectional"))
    )
    (net (code "310") (name "unconnected-(U$2-NC-PadH7)") (class "Default")
      (node (ref "U$2") (pin "H7") (pinfunction "NC_H7") (pintype "bidirectional"))
    )
    (net (code "311") (name "unconnected-(U$2-NC-PadJ1)") (class "Default")
      (node (ref "U$2") (pin "J1") (pinfunction "NC_J1") (pintype "bidirectional"))
    )
    (net (code "312") (name "unconnected-(U$2-NC-PadK1)") (class "Default")
      (node (ref "U$2") (pin "K1") (pinfunction "NC_K1") (pintype "bidirectional"))
    )
    (net (code "313") (name "unconnected-(U$2-NC-PadL2)") (class "Default")
      (node (ref "U$2") (pin "L2") (pinfunction "NC_L2") (pintype "bidirectional"))
    )
    (net (code "314") (name "unconnected-(U$2-NC-PadL6)") (class "Default")
      (node (ref "U$2") (pin "L6") (pinfunction "NC_L6") (pintype "bidirectional"))
    )
    (net (code "315") (name "unconnected-(U1A-GBUF-Pad42)") (class "Default")
      (node (ref "U1") (pin "42") (pinfunction "GBUF_42") (pintype "output"))
    )
    (net (code "316") (name "unconnected-(U1A-LEFT-Pad46)") (class "Default")
      (node (ref "U1") (pin "46") (pinfunction "LEFT_46") (pintype "output"))
    )
    (net (code "317") (name "unconnected-(U1A-LINEINR-Pad48)") (class "Default")
      (node (ref "U1") (pin "48") (pinfunction "LINEINR_48") (pintype "input"))
    )
    (net (code "318") (name "unconnected-(U1A-MICN-Pad2)") (class "Default")
      (node (ref "U1") (pin "2") (pinfunction "MICN_2") (pintype "input"))
    )
    (net (code "319") (name "unconnected-(U1A-MICP{slash}LINEINL-Pad1)") (class "Default")
      (node (ref "U1") (pin "1") (pinfunction "MICP/LINEINL_1") (pintype "input"))
    )
    (net (code "320") (name "unconnected-(U1A-RCAP-Pad44)") (class "Default")
      (node (ref "U1") (pin "44") (pinfunction "RCAP_44") (pintype "bidirectional"))
    )
    (net (code "321") (name "unconnected-(U1A-RIGHT-Pad39)") (class "Default")
      (node (ref "U1") (pin "39") (pinfunction "RIGHT_39") (pintype "output"))
    )
  )
)
